# PICO_LCD.net
KiCad netlist of a schematic drawn in Altium Designer
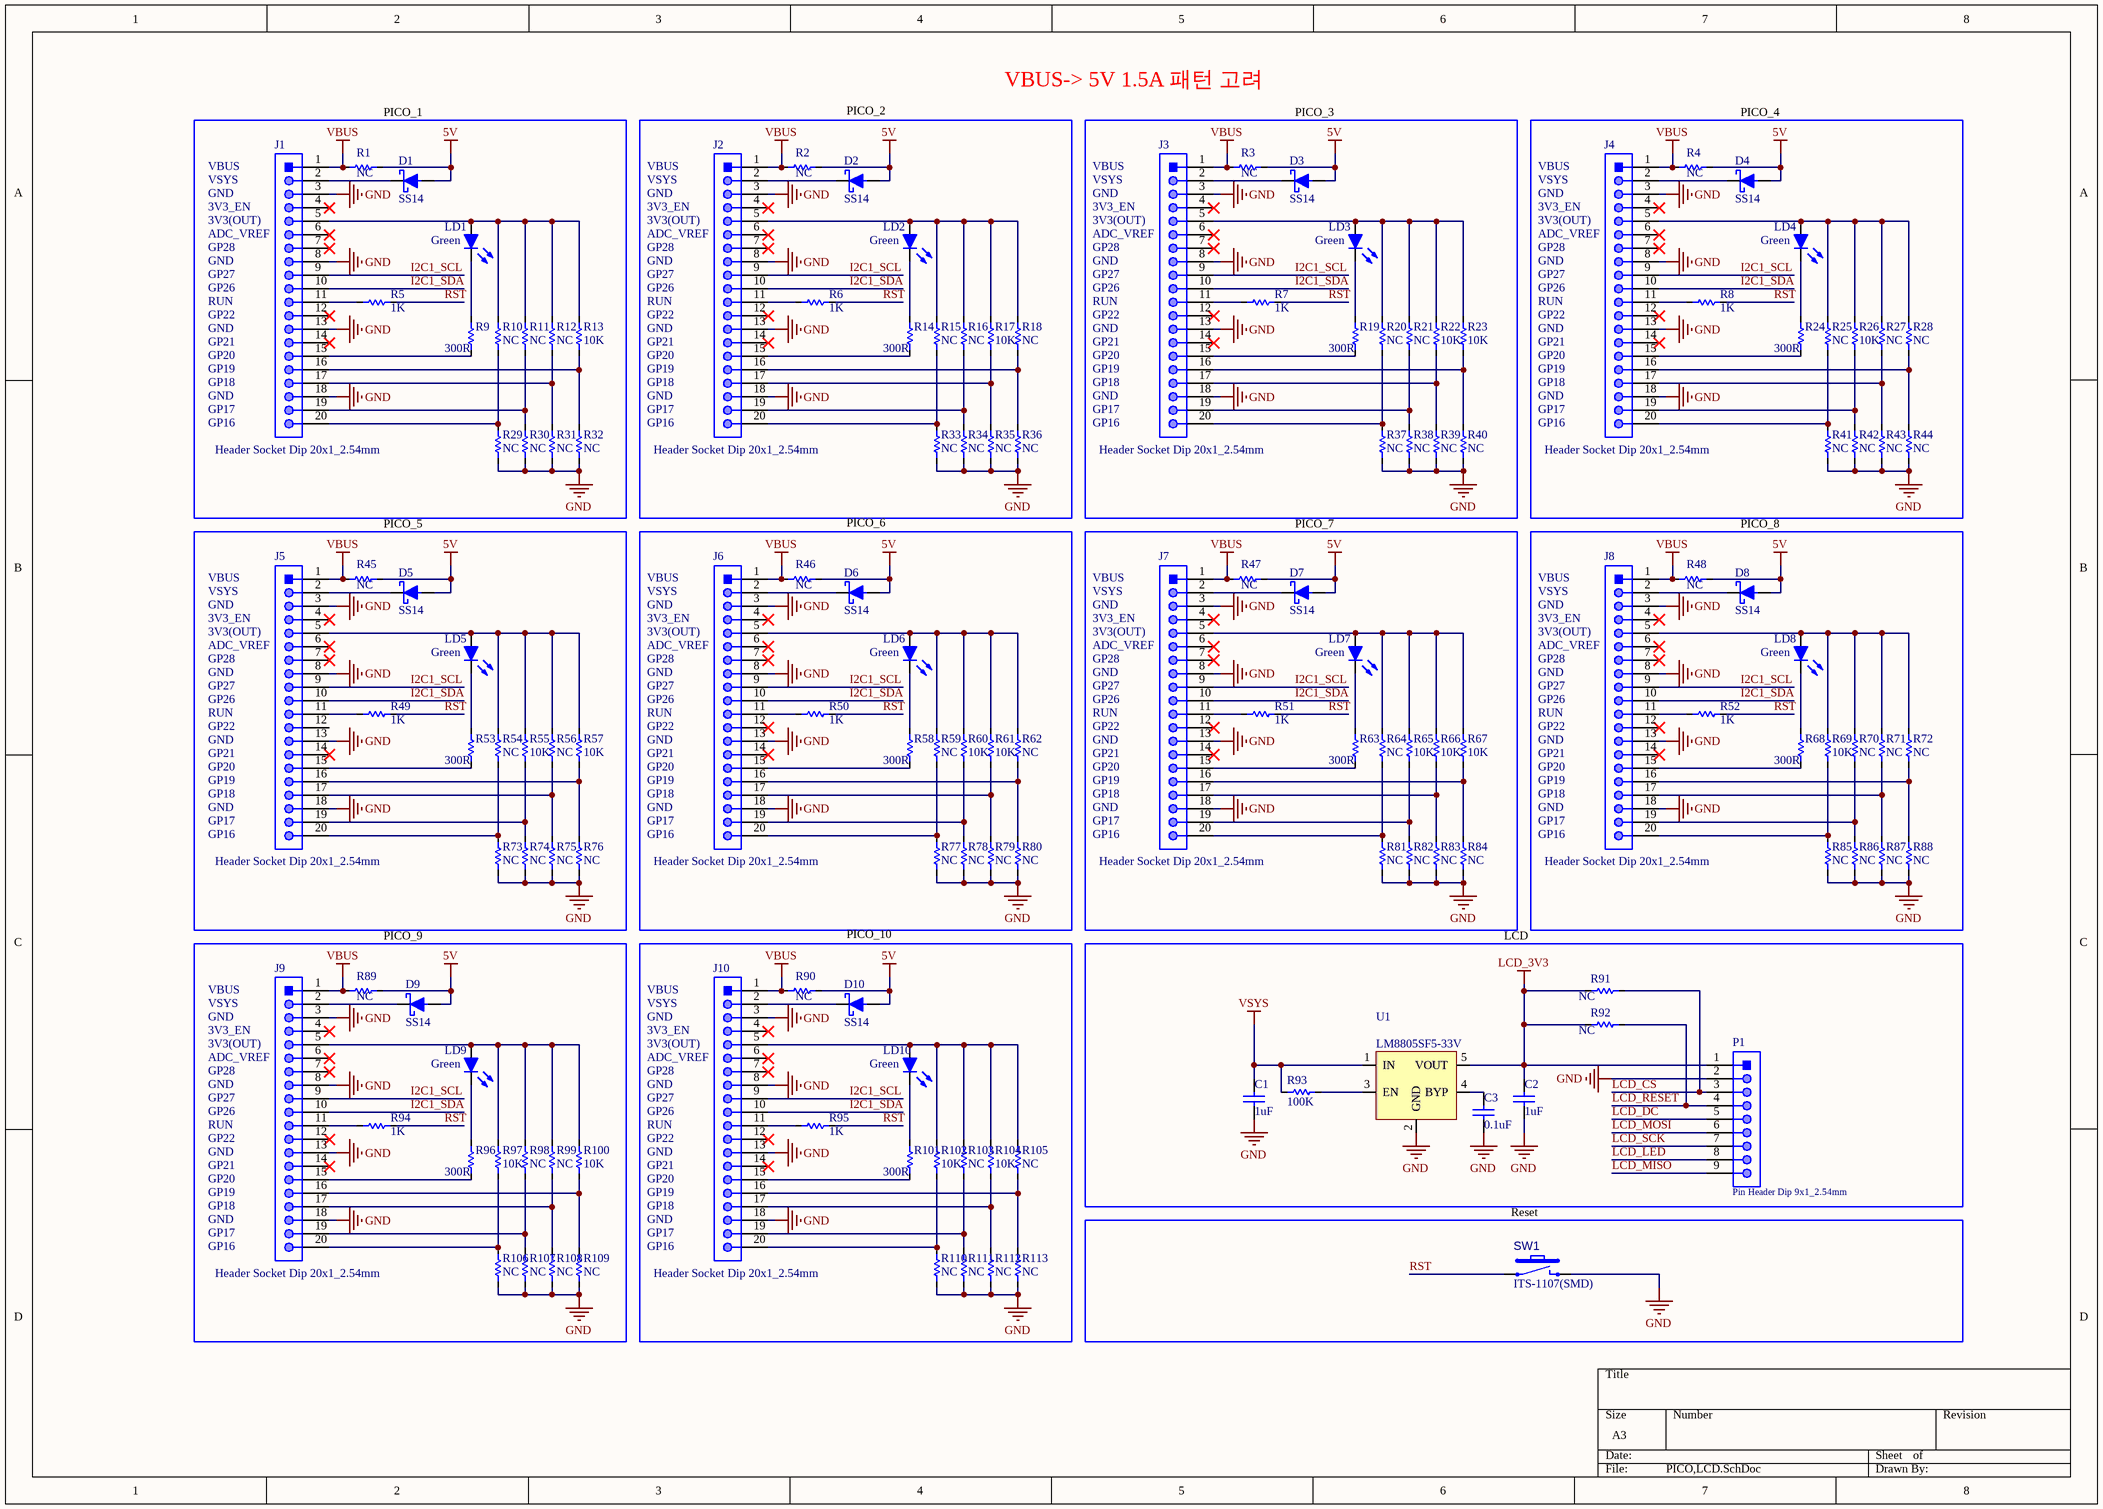
[diagram p0: PICO,LCD.SchDoc]

(export (version "E")
  (design (tool "Eeschema 10.0.6"))
  (components
    (comp (ref "C1")
      (value "1uF")
      (footprint "CAP-0603")
      (description "MLCC-0603(1608)")
      (libsource (lib "Jaden_Lib") (part "CAP-0603"))
    )
    (comp (ref "C2")
      (value "1uF")
      (footprint "CAP-0603")
      (description "MLCC-0603(1608)")
      (libsource (lib "Jaden_Lib") (part "CAP-0603"))
    )
    (comp (ref "C3")
      (value "0.1uF")
      (footprint "CAP-0603")
      (description "MLCC-0603(1608)")
      (libsource (lib "Jaden_Lib") (part "CAP-0603"))
    )
    (comp (ref "D1")
      (value "SS14")
      (footprint "DO-214AC/SMA")
      (description "DIODE SCHOTTKY 40V 1A SMA")
      (fields
        (field (name "MANUFACTURER") "ON Semiconductor")
        (field (name "OCTOPART") "https://octopart.com/ss14-on+semiconductor-29205033")
      )
      (libsource (lib "Jaden_Lib") (part "DIODE-Shottky SMA(DO-214AC)"))
    )
    (comp (ref "D2")
      (value "SS14")
      (footprint "DO-214AC/SMA")
      (description "DIODE SCHOTTKY 40V 1A SMA")
      (fields
        (field (name "MANUFACTURER") "ON Semiconductor")
        (field (name "OCTOPART") "https://octopart.com/ss14-on+semiconductor-29205033")
      )
      (libsource (lib "Jaden_Lib") (part "DIODE-Shottky SMA(DO-214AC)"))
    )
    (comp (ref "D3")
      (value "SS14")
      (footprint "DO-214AC/SMA")
      (description "DIODE SCHOTTKY 40V 1A SMA")
      (fields
        (field (name "MANUFACTURER") "ON Semiconductor")
        (field (name "OCTOPART") "https://octopart.com/ss14-on+semiconductor-29205033")
      )
      (libsource (lib "Jaden_Lib") (part "DIODE-Shottky SMA(DO-214AC)"))
    )
    (comp (ref "D4")
      (value "SS14")
      (footprint "DO-214AC/SMA")
      (description "DIODE SCHOTTKY 40V 1A SMA")
      (fields
        (field (name "MANUFACTURER") "ON Semiconductor")
        (field (name "OCTOPART") "https://octopart.com/ss14-on+semiconductor-29205033")
      )
      (libsource (lib "Jaden_Lib") (part "DIODE-Shottky SMA(DO-214AC)"))
    )
    (comp (ref "D5")
      (value "SS14")
      (footprint "DO-214AC/SMA")
      (description "DIODE SCHOTTKY 40V 1A SMA")
      (fields
        (field (name "MANUFACTURER") "ON Semiconductor")
        (field (name "OCTOPART") "https://octopart.com/ss14-on+semiconductor-29205033")
      )
      (libsource (lib "Jaden_Lib") (part "DIODE-Shottky SMA(DO-214AC)"))
    )
    (comp (ref "D6")
      (value "SS14")
      (footprint "DO-214AC/SMA")
      (description "DIODE SCHOTTKY 40V 1A SMA")
      (fields
        (field (name "MANUFACTURER") "ON Semiconductor")
        (field (name "OCTOPART") "https://octopart.com/ss14-on+semiconductor-29205033")
      )
      (libsource (lib "Jaden_Lib") (part "DIODE-Shottky SMA(DO-214AC)"))
    )
    (comp (ref "D7")
      (value "SS14")
      (footprint "DO-214AC/SMA")
      (description "DIODE SCHOTTKY 40V 1A SMA")
      (fields
        (field (name "MANUFACTURER") "ON Semiconductor")
        (field (name "OCTOPART") "https://octopart.com/ss14-on+semiconductor-29205033")
      )
      (libsource (lib "Jaden_Lib") (part "DIODE-Shottky SMA(DO-214AC)"))
    )
    (comp (ref "D8")
      (value "SS14")
      (footprint "DO-214AC/SMA")
      (description "DIODE SCHOTTKY 40V 1A SMA")
      (fields
        (field (name "MANUFACTURER") "ON Semiconductor")
        (field (name "OCTOPART") "https://octopart.com/ss14-on+semiconductor-29205033")
      )
      (libsource (lib "Jaden_Lib") (part "DIODE-Shottky SMA(DO-214AC)"))
    )
    (comp (ref "D9")
      (value "SS14")
      (footprint "DO-214AC/SMA")
      (description "DIODE SCHOTTKY 40V 1A SMA")
      (fields
        (field (name "MANUFACTURER") "ON Semiconductor")
        (field (name "OCTOPART") "https://octopart.com/ss14-on+semiconductor-29205033")
      )
      (libsource (lib "Jaden_Lib") (part "DIODE-Shottky SMA(DO-214AC)"))
    )
    (comp (ref "D10")
      (value "SS14")
      (footprint "DO-214AC/SMA")
      (description "DIODE SCHOTTKY 40V 1A SMA")
      (fields
        (field (name "MANUFACTURER") "ON Semiconductor")
        (field (name "OCTOPART") "https://octopart.com/ss14-on+semiconductor-29205033")
      )
      (libsource (lib "Jaden_Lib") (part "DIODE-Shottky SMA(DO-214AC)"))
    )
    (comp (ref "J1")
      (value "Header Socket Dip 20x1_2.54mm")
      (footprint "IDC-1X20(SOCKET)")
      (description "THT Vertical Header Socket WR-PHD, Pitch 2.54 mm, Single Row, 20 pins")
      (fields
        (field (name "MANUFACTURER_PART_NUMBER") "M20-7822046")
        (field (name "MOUSER PART NUMBER") "855-M20-7822046")
      )
      (libsource (lib "Jaden_Lib") (part "Header Socket 20x1_2.54mm"))
    )
    (comp (ref "J2")
      (value "Header Socket Dip 20x1_2.54mm")
      (footprint "IDC-1X20(SOCKET)")
      (description "THT Vertical Header Socket WR-PHD, Pitch 2.54 mm, Single Row, 20 pins")
      (fields
        (field (name "MANUFACTURER_PART_NUMBER") "M20-7822046")
        (field (name "MOUSER PART NUMBER") "855-M20-7822046")
      )
      (libsource (lib "Jaden_Lib") (part "Header Socket 20x1_2.54mm"))
    )
    (comp (ref "J3")
      (value "Header Socket Dip 20x1_2.54mm")
      (footprint "IDC-1X20(SOCKET)")
      (description "THT Vertical Header Socket WR-PHD, Pitch 2.54 mm, Single Row, 20 pins")
      (fields
        (field (name "MANUFACTURER_PART_NUMBER") "M20-7822046")
        (field (name "MOUSER PART NUMBER") "855-M20-7822046")
      )
      (libsource (lib "Jaden_Lib") (part "Header Socket 20x1_2.54mm"))
    )
    (comp (ref "J4")
      (value "Header Socket Dip 20x1_2.54mm")
      (footprint "IDC-1X20(SOCKET)")
      (description "THT Vertical Header Socket WR-PHD, Pitch 2.54 mm, Single Row, 20 pins")
      (fields
        (field (name "MANUFACTURER_PART_NUMBER") "M20-7822046")
        (field (name "MOUSER PART NUMBER") "855-M20-7822046")
      )
      (libsource (lib "Jaden_Lib") (part "Header Socket 20x1_2.54mm"))
    )
    (comp (ref "J5")
      (value "Header Socket Dip 20x1_2.54mm")
      (footprint "IDC-1X20(SOCKET)")
      (description "THT Vertical Header Socket WR-PHD, Pitch 2.54 mm, Single Row, 20 pins")
      (fields
        (field (name "MANUFACTURER_PART_NUMBER") "M20-7822046")
        (field (name "MOUSER PART NUMBER") "855-M20-7822046")
      )
      (libsource (lib "Jaden_Lib") (part "Header Socket 20x1_2.54mm"))
    )
    (comp (ref "J6")
      (value "Header Socket Dip 20x1_2.54mm")
      (footprint "IDC-1X20(SOCKET)")
      (description "THT Vertical Header Socket WR-PHD, Pitch 2.54 mm, Single Row, 20 pins")
      (fields
        (field (name "MANUFACTURER_PART_NUMBER") "M20-7822046")
        (field (name "MOUSER PART NUMBER") "855-M20-7822046")
      )
      (libsource (lib "Jaden_Lib") (part "Header Socket 20x1_2.54mm"))
    )
    (comp (ref "J7")
      (value "Header Socket Dip 20x1_2.54mm")
      (footprint "IDC-1X20(SOCKET)")
      (description "THT Vertical Header Socket WR-PHD, Pitch 2.54 mm, Single Row, 20 pins")
      (fields
        (field (name "MANUFACTURER_PART_NUMBER") "M20-7822046")
        (field (name "MOUSER PART NUMBER") "855-M20-7822046")
      )
      (libsource (lib "Jaden_Lib") (part "Header Socket 20x1_2.54mm"))
    )
    (comp (ref "J8")
      (value "Header Socket Dip 20x1_2.54mm")
      (footprint "IDC-1X20(SOCKET)")
      (description "THT Vertical Header Socket WR-PHD, Pitch 2.54 mm, Single Row, 20 pins")
      (fields
        (field (name "MANUFACTURER_PART_NUMBER") "M20-7822046")
        (field (name "MOUSER PART NUMBER") "855-M20-7822046")
      )
      (libsource (lib "Jaden_Lib") (part "Header Socket 20x1_2.54mm"))
    )
    (comp (ref "J9")
      (value "Header Socket Dip 20x1_2.54mm")
      (footprint "IDC-1X20(SOCKET)")
      (description "THT Vertical Header Socket WR-PHD, Pitch 2.54 mm, Single Row, 20 pins")
      (fields
        (field (name "MANUFACTURER_PART_NUMBER") "M20-7822046")
        (field (name "MOUSER PART NUMBER") "855-M20-7822046")
      )
      (libsource (lib "Jaden_Lib") (part "Header Socket 20x1_2.54mm"))
    )
    (comp (ref "J10")
      (value "Header Socket Dip 20x1_2.54mm")
      (footprint "IDC-1X20(SOCKET)")
      (description "THT Vertical Header Socket WR-PHD, Pitch 2.54 mm, Single Row, 20 pins")
      (fields
        (field (name "MANUFACTURER_PART_NUMBER") "M20-7822046")
        (field (name "MOUSER PART NUMBER") "855-M20-7822046")
      )
      (libsource (lib "Jaden_Lib") (part "Header Socket 20x1_2.54mm"))
    )
    (comp (ref "LD1")
      (value "Green")
      (footprint "LED-0603-GREEN")
      (description "LED-0603")
      (libsource (lib "Jaden_Lib") (part "GREEN LED-0603"))
    )
    (comp (ref "LD2")
      (value "Green")
      (footprint "LED-0603-GREEN")
      (description "LED-0603")
      (libsource (lib "Jaden_Lib") (part "GREEN LED-0603"))
    )
    (comp (ref "LD3")
      (value "Green")
      (footprint "LED-0603-GREEN")
      (description "LED-0603")
      (libsource (lib "Jaden_Lib") (part "GREEN LED-0603"))
    )
    (comp (ref "LD4")
      (value "Green")
      (footprint "LED-0603-GREEN")
      (description "LED-0603")
      (libsource (lib "Jaden_Lib") (part "GREEN LED-0603"))
    )
    (comp (ref "LD5")
      (value "Green")
      (footprint "LED-0603-GREEN")
      (description "LED-0603")
      (libsource (lib "Jaden_Lib") (part "GREEN LED-0603"))
    )
    (comp (ref "LD6")
      (value "Green")
      (footprint "LED-0603-GREEN")
      (description "LED-0603")
      (libsource (lib "Jaden_Lib") (part "GREEN LED-0603"))
    )
    (comp (ref "LD7")
      (value "Green")
      (footprint "LED-0603-GREEN")
      (description "LED-0603")
      (libsource (lib "Jaden_Lib") (part "GREEN LED-0603"))
    )
    (comp (ref "LD8")
      (value "Green")
      (footprint "LED-0603-GREEN")
      (description "LED-0603")
      (libsource (lib "Jaden_Lib") (part "GREEN LED-0603"))
    )
    (comp (ref "LD9")
      (value "Green")
      (footprint "LED-0603-GREEN")
      (description "LED-0603")
      (libsource (lib "Jaden_Lib") (part "GREEN LED-0603"))
    )
    (comp (ref "LD10")
      (value "Green")
      (footprint "LED-0603-GREEN")
      (description "LED-0603")
      (libsource (lib "Jaden_Lib") (part "GREEN LED-0603"))
    )
    (comp (ref "P1")
      (value "Pin Header Dip 9x1_2.54mm")
      (footprint "LCD(PIN HEADER9X1_2.54)")
      (description "THT Vertical Pin Header WR-PHD, Pitch 2.54 mm, Single Row, 9 pins")
      (fields
        (field (name "PART NUMBER") "61300911121")
        (field (name "MANUFACTURER") "Wurth Elektronik")
        (field (name "PUBLISHER") "WurthElektronik")
      )
      (libsource (lib "Jaden_Lib") (part "Pin Header 9x1_2.54mm"))
    )
    (comp (ref "R1")
      (value "NC")
      (footprint "RES-0603")
      (description "Chip Resistor 0603(1608)")
      (fields (field (name "TOLERANCE") "1%") (field (name "MANUFACTURER") "Yageo"))
      (libsource (lib "Jaden_Lib") (part "RES-0603"))
    )
    (comp (ref "R2")
      (value "NC")
      (footprint "RES-0603")
      (description "Chip Resistor 0603(1608)")
      (fields (field (name "TOLERANCE") "1%") (field (name "MANUFACTURER") "Yageo"))
      (libsource (lib "Jaden_Lib") (part "RES-0603"))
    )
    (comp (ref "R3")
      (value "NC")
      (footprint "RES-0603")
      (description "Chip Resistor 0603(1608)")
      (fields (field (name "TOLERANCE") "1%") (field (name "MANUFACTURER") "Yageo"))
      (libsource (lib "Jaden_Lib") (part "RES-0603"))
    )
    (comp (ref "R4")
      (value "NC")
      (footprint "RES-0603")
      (description "Chip Resistor 0603(1608)")
      (fields (field (name "TOLERANCE") "1%") (field (name "MANUFACTURER") "Yageo"))
      (libsource (lib "Jaden_Lib") (part "RES-0603"))
    )
    (comp (ref "R5")
      (value "1K")
      (footprint "RES-0603")
      (description "Chip Resistor 0603(1608)")
      (fields (field (name "TOLERANCE") "1%") (field (name "MANUFACTURER") "Yageo"))
      (libsource (lib "Jaden_Lib") (part "RES-0603"))
    )
    (comp (ref "R6")
      (value "1K")
      (footprint "RES-0603")
      (description "Chip Resistor 0603(1608)")
      (fields (field (name "TOLERANCE") "1%") (field (name "MANUFACTURER") "Yageo"))
      (libsource (lib "Jaden_Lib") (part "RES-0603"))
    )
    (comp (ref "R7")
      (value "1K")
      (footprint "RES-0603")
      (description "Chip Resistor 0603(1608)")
      (fields (field (name "TOLERANCE") "1%") (field (name "MANUFACTURER") "Yageo"))
      (libsource (lib "Jaden_Lib") (part "RES-0603"))
    )
    (comp (ref "R8")
      (value "1K")
      (footprint "RES-0603")
      (description "Chip Resistor 0603(1608)")
      (fields (field (name "TOLERANCE") "1%") (field (name "MANUFACTURER") "Yageo"))
      (libsource (lib "Jaden_Lib") (part "RES-0603"))
    )
    (comp (ref "R9")
      (value "300R")
      (footprint "RES-0603")
      (description "Chip Resistor 0603(1608)")
      (fields (field (name "TOLERANCE") "1%") (field (name "MANUFACTURER") "Yageo"))
      (libsource (lib "Jaden_Lib") (part "RES-0603"))
    )
    (comp (ref "R10")
      (value "NC")
      (footprint "RES-0603")
      (description "Chip Resistor 0603(1608)")
      (fields (field (name "TOLERANCE") "1%") (field (name "MANUFACTURER") "Yageo"))
      (libsource (lib "Jaden_Lib") (part "RES-0603"))
    )
    (comp (ref "R11")
      (value "NC")
      (footprint "RES-0603")
      (description "Chip Resistor 0603(1608)")
      (fields (field (name "TOLERANCE") "1%") (field (name "MANUFACTURER") "Yageo"))
      (libsource (lib "Jaden_Lib") (part "RES-0603"))
    )
    (comp (ref "R12")
      (value "NC")
      (footprint "RES-0603")
      (description "Chip Resistor 0603(1608)")
      (fields (field (name "TOLERANCE") "1%") (field (name "MANUFACTURER") "Yageo"))
      (libsource (lib "Jaden_Lib") (part "RES-0603"))
    )
    (comp (ref "R13")
      (value "10K")
      (footprint "RES-0603")
      (description "Chip Resistor 0603(1608)")
      (fields (field (name "TOLERANCE") "1%") (field (name "MANUFACTURER") "Yageo"))
      (libsource (lib "Jaden_Lib") (part "RES-0603"))
    )
    (comp (ref "R14")
      (value "300R")
      (footprint "RES-0603")
      (description "Chip Resistor 0603(1608)")
      (fields (field (name "TOLERANCE") "1%") (field (name "MANUFACTURER") "Yageo"))
      (libsource (lib "Jaden_Lib") (part "RES-0603"))
    )
    (comp (ref "R15")
      (value "NC")
      (footprint "RES-0603")
      (description "Chip Resistor 0603(1608)")
      (fields (field (name "TOLERANCE") "1%") (field (name "MANUFACTURER") "Yageo"))
      (libsource (lib "Jaden_Lib") (part "RES-0603"))
    )
    (comp (ref "R16")
      (value "NC")
      (footprint "RES-0603")
      (description "Chip Resistor 0603(1608)")
      (fields (field (name "TOLERANCE") "1%") (field (name "MANUFACTURER") "Yageo"))
      (libsource (lib "Jaden_Lib") (part "RES-0603"))
    )
    (comp (ref "R17")
      (value "10K")
      (footprint "RES-0603")
      (description "Chip Resistor 0603(1608)")
      (fields (field (name "TOLERANCE") "1%") (field (name "MANUFACTURER") "Yageo"))
      (libsource (lib "Jaden_Lib") (part "RES-0603"))
    )
    (comp (ref "R18")
      (value "NC")
      (footprint "RES-0603")
      (description "Chip Resistor 0603(1608)")
      (fields (field (name "TOLERANCE") "1%") (field (name "MANUFACTURER") "Yageo"))
      (libsource (lib "Jaden_Lib") (part "RES-0603"))
    )
    (comp (ref "R19")
      (value "300R")
      (footprint "RES-0603")
      (description "Chip Resistor 0603(1608)")
      (fields (field (name "TOLERANCE") "1%") (field (name "MANUFACTURER") "Yageo"))
      (libsource (lib "Jaden_Lib") (part "RES-0603"))
    )
    (comp (ref "R20")
      (value "NC")
      (footprint "RES-0603")
      (description "Chip Resistor 0603(1608)")
      (fields (field (name "TOLERANCE") "1%") (field (name "MANUFACTURER") "Yageo"))
      (libsource (lib "Jaden_Lib") (part "RES-0603"))
    )
    (comp (ref "R21")
      (value "NC")
      (footprint "RES-0603")
      (description "Chip Resistor 0603(1608)")
      (fields (field (name "TOLERANCE") "1%") (field (name "MANUFACTURER") "Yageo"))
      (libsource (lib "Jaden_Lib") (part "RES-0603"))
    )
    (comp (ref "R22")
      (value "10K")
      (footprint "RES-0603")
      (description "Chip Resistor 0603(1608)")
      (fields (field (name "TOLERANCE") "1%") (field (name "MANUFACTURER") "Yageo"))
      (libsource (lib "Jaden_Lib") (part "RES-0603"))
    )
    (comp (ref "R23")
      (value "10K")
      (footprint "RES-0603")
      (description "Chip Resistor 0603(1608)")
      (fields (field (name "TOLERANCE") "1%") (field (name "MANUFACTURER") "Yageo"))
      (libsource (lib "Jaden_Lib") (part "RES-0603"))
    )
    (comp (ref "R24")
      (value "300R")
      (footprint "RES-0603")
      (description "Chip Resistor 0603(1608)")
      (fields (field (name "TOLERANCE") "1%") (field (name "MANUFACTURER") "Yageo"))
      (libsource (lib "Jaden_Lib") (part "RES-0603"))
    )
    (comp (ref "R25")
      (value "NC")
      (footprint "RES-0603")
      (description "Chip Resistor 0603(1608)")
      (fields (field (name "TOLERANCE") "1%") (field (name "MANUFACTURER") "Yageo"))
      (libsource (lib "Jaden_Lib") (part "RES-0603"))
    )
    (comp (ref "R26")
      (value "10K")
      (footprint "RES-0603")
      (description "Chip Resistor 0603(1608)")
      (fields (field (name "TOLERANCE") "1%") (field (name "MANUFACTURER") "Yageo"))
      (libsource (lib "Jaden_Lib") (part "RES-0603"))
    )
    (comp (ref "R27")
      (value "NC")
      (footprint "RES-0603")
      (description "Chip Resistor 0603(1608)")
      (fields (field (name "TOLERANCE") "1%") (field (name "MANUFACTURER") "Yageo"))
      (libsource (lib "Jaden_Lib") (part "RES-0603"))
    )
    (comp (ref "R28")
      (value "NC")
      (footprint "RES-0603")
      (description "Chip Resistor 0603(1608)")
      (fields (field (name "TOLERANCE") "1%") (field (name "MANUFACTURER") "Yageo"))
      (libsource (lib "Jaden_Lib") (part "RES-0603"))
    )
    (comp (ref "R29")
      (value "NC")
      (footprint "RES-0603")
      (description "Chip Resistor 0603(1608)")
      (fields (field (name "TOLERANCE") "1%") (field (name "MANUFACTURER") "Yageo"))
      (libsource (lib "Jaden_Lib") (part "RES-0603"))
    )
    (comp (ref "R30")
      (value "NC")
      (footprint "RES-0603")
      (description "Chip Resistor 0603(1608)")
      (fields (field (name "TOLERANCE") "1%") (field (name "MANUFACTURER") "Yageo"))
      (libsource (lib "Jaden_Lib") (part "RES-0603"))
    )
    (comp (ref "R31")
      (value "NC")
      (footprint "RES-0603")
      (description "Chip Resistor 0603(1608)")
      (fields (field (name "TOLERANCE") "1%") (field (name "MANUFACTURER") "Yageo"))
      (libsource (lib "Jaden_Lib") (part "RES-0603"))
    )
    (comp (ref "R32")
      (value "NC")
      (footprint "RES-0603")
      (description "Chip Resistor 0603(1608)")
      (fields (field (name "TOLERANCE") "1%") (field (name "MANUFACTURER") "Yageo"))
      (libsource (lib "Jaden_Lib") (part "RES-0603"))
    )
    (comp (ref "R33")
      (value "NC")
      (footprint "RES-0603")
      (description "Chip Resistor 0603(1608)")
      (fields (field (name "TOLERANCE") "1%") (field (name "MANUFACTURER") "Yageo"))
      (libsource (lib "Jaden_Lib") (part "RES-0603"))
    )
    (comp (ref "R34")
      (value "NC")
      (footprint "RES-0603")
      (description "Chip Resistor 0603(1608)")
      (fields (field (name "TOLERANCE") "1%") (field (name "MANUFACTURER") "Yageo"))
      (libsource (lib "Jaden_Lib") (part "RES-0603"))
    )
    (comp (ref "R35")
      (value "NC")
      (footprint "RES-0603")
      (description "Chip Resistor 0603(1608)")
      (fields (field (name "TOLERANCE") "1%") (field (name "MANUFACTURER") "Yageo"))
      (libsource (lib "Jaden_Lib") (part "RES-0603"))
    )
    (comp (ref "R36")
      (value "NC")
      (footprint "RES-0603")
      (description "Chip Resistor 0603(1608)")
      (fields (field (name "TOLERANCE") "1%") (field (name "MANUFACTURER") "Yageo"))
      (libsource (lib "Jaden_Lib") (part "RES-0603"))
    )
    (comp (ref "R37")
      (value "NC")
      (footprint "RES-0603")
      (description "Chip Resistor 0603(1608)")
      (fields (field (name "TOLERANCE") "1%") (field (name "MANUFACTURER") "Yageo"))
      (libsource (lib "Jaden_Lib") (part "RES-0603"))
    )
    (comp (ref "R38")
      (value "NC")
      (footprint "RES-0603")
      (description "Chip Resistor 0603(1608)")
      (fields (field (name "TOLERANCE") "1%") (field (name "MANUFACTURER") "Yageo"))
      (libsource (lib "Jaden_Lib") (part "RES-0603"))
    )
    (comp (ref "R39")
      (value "NC")
      (footprint "RES-0603")
      (description "Chip Resistor 0603(1608)")
      (fields (field (name "TOLERANCE") "1%") (field (name "MANUFACTURER") "Yageo"))
      (libsource (lib "Jaden_Lib") (part "RES-0603"))
    )
    (comp (ref "R40")
      (value "NC")
      (footprint "RES-0603")
      (description "Chip Resistor 0603(1608)")
      (fields (field (name "TOLERANCE") "1%") (field (name "MANUFACTURER") "Yageo"))
      (libsource (lib "Jaden_Lib") (part "RES-0603"))
    )
    (comp (ref "R41")
      (value "NC")
      (footprint "RES-0603")
      (description "Chip Resistor 0603(1608)")
      (fields (field (name "TOLERANCE") "1%") (field (name "MANUFACTURER") "Yageo"))
      (libsource (lib "Jaden_Lib") (part "RES-0603"))
    )
    (comp (ref "R42")
      (value "NC")
      (footprint "RES-0603")
      (description "Chip Resistor 0603(1608)")
      (fields (field (name "TOLERANCE") "1%") (field (name "MANUFACTURER") "Yageo"))
      (libsource (lib "Jaden_Lib") (part "RES-0603"))
    )
    (comp (ref "R43")
      (value "NC")
      (footprint "RES-0603")
      (description "Chip Resistor 0603(1608)")
      (fields (field (name "TOLERANCE") "1%") (field (name "MANUFACTURER") "Yageo"))
      (libsource (lib "Jaden_Lib") (part "RES-0603"))
    )
    (comp (ref "R44")
      (value "NC")
      (footprint "RES-0603")
      (description "Chip Resistor 0603(1608)")
      (fields (field (name "TOLERANCE") "1%") (field (name "MANUFACTURER") "Yageo"))
      (libsource (lib "Jaden_Lib") (part "RES-0603"))
    )
    (comp (ref "R45")
      (value "NC")
      (footprint "RES-0603")
      (description "Chip Resistor 0603(1608)")
      (fields (field (name "TOLERANCE") "1%") (field (name "MANUFACTURER") "Yageo"))
      (libsource (lib "Jaden_Lib") (part "RES-0603"))
    )
    (comp (ref "R46")
      (value "NC")
      (footprint "RES-0603")
      (description "Chip Resistor 0603(1608)")
      (fields (field (name "TOLERANCE") "1%") (field (name "MANUFACTURER") "Yageo"))
      (libsource (lib "Jaden_Lib") (part "RES-0603"))
    )
    (comp (ref "R47")
      (value "NC")
      (footprint "RES-0603")
      (description "Chip Resistor 0603(1608)")
      (fields (field (name "TOLERANCE") "1%") (field (name "MANUFACTURER") "Yageo"))
      (libsource (lib "Jaden_Lib") (part "RES-0603"))
    )
    (comp (ref "R48")
      (value "NC")
      (footprint "RES-0603")
      (description "Chip Resistor 0603(1608)")
      (fields (field (name "TOLERANCE") "1%") (field (name "MANUFACTURER") "Yageo"))
      (libsource (lib "Jaden_Lib") (part "RES-0603"))
    )
    (comp (ref "R49")
      (value "1K")
      (footprint "RES-0603")
      (description "Chip Resistor 0603(1608)")
      (fields (field (name "TOLERANCE") "1%") (field (name "MANUFACTURER") "Yageo"))
      (libsource (lib "Jaden_Lib") (part "RES-0603"))
    )
    (comp (ref "R50")
      (value "1K")
      (footprint "RES-0603")
      (description "Chip Resistor 0603(1608)")
      (fields (field (name "TOLERANCE") "1%") (field (name "MANUFACTURER") "Yageo"))
      (libsource (lib "Jaden_Lib") (part "RES-0603"))
    )
    (comp (ref "R51")
      (value "1K")
      (footprint "RES-0603")
      (description "Chip Resistor 0603(1608)")
      (fields (field (name "TOLERANCE") "1%") (field (name "MANUFACTURER") "Yageo"))
      (libsource (lib "Jaden_Lib") (part "RES-0603"))
    )
    (comp (ref "R52")
      (value "1K")
      (footprint "RES-0603")
      (description "Chip Resistor 0603(1608)")
      (fields (field (name "TOLERANCE") "1%") (field (name "MANUFACTURER") "Yageo"))
      (libsource (lib "Jaden_Lib") (part "RES-0603"))
    )
    (comp (ref "R53")
      (value "300R")
      (footprint "RES-0603")
      (description "Chip Resistor 0603(1608)")
      (fields (field (name "TOLERANCE") "1%") (field (name "MANUFACTURER") "Yageo"))
      (libsource (lib "Jaden_Lib") (part "RES-0603"))
    )
    (comp (ref "R54")
      (value "NC")
      (footprint "RES-0603")
      (description "Chip Resistor 0603(1608)")
      (fields (field (name "TOLERANCE") "1%") (field (name "MANUFACTURER") "Yageo"))
      (libsource (lib "Jaden_Lib") (part "RES-0603"))
    )
    (comp (ref "R55")
      (value "10K")
      (footprint "RES-0603")
      (description "Chip Resistor 0603(1608)")
      (fields (field (name "TOLERANCE") "1%") (field (name "MANUFACTURER") "Yageo"))
      (libsource (lib "Jaden_Lib") (part "RES-0603"))
    )
    (comp (ref "R56")
      (value "NC")
      (footprint "RES-0603")
      (description "Chip Resistor 0603(1608)")
      (fields (field (name "TOLERANCE") "1%") (field (name "MANUFACTURER") "Yageo"))
      (libsource (lib "Jaden_Lib") (part "RES-0603"))
    )
    (comp (ref "R57")
      (value "10K")
      (footprint "RES-0603")
      (description "Chip Resistor 0603(1608)")
      (fields (field (name "TOLERANCE") "1%") (field (name "MANUFACTURER") "Yageo"))
      (libsource (lib "Jaden_Lib") (part "RES-0603"))
    )
    (comp (ref "R58")
      (value "300R")
      (footprint "RES-0603")
      (description "Chip Resistor 0603(1608)")
      (fields (field (name "TOLERANCE") "1%") (field (name "MANUFACTURER") "Yageo"))
      (libsource (lib "Jaden_Lib") (part "RES-0603"))
    )
    (comp (ref "R59")
      (value "NC")
      (footprint "RES-0603")
      (description "Chip Resistor 0603(1608)")
      (fields (field (name "TOLERANCE") "1%") (field (name "MANUFACTURER") "Yageo"))
      (libsource (lib "Jaden_Lib") (part "RES-0603"))
    )
    (comp (ref "R60")
      (value "10K")
      (footprint "RES-0603")
      (description "Chip Resistor 0603(1608)")
      (fields (field (name "TOLERANCE") "1%") (field (name "MANUFACTURER") "Yageo"))
      (libsource (lib "Jaden_Lib") (part "RES-0603"))
    )
    (comp (ref "R61")
      (value "10K")
      (footprint "RES-0603")
      (description "Chip Resistor 0603(1608)")
      (fields (field (name "TOLERANCE") "1%") (field (name "MANUFACTURER") "Yageo"))
      (libsource (lib "Jaden_Lib") (part "RES-0603"))
    )
    (comp (ref "R62")
      (value "NC")
      (footprint "RES-0603")
      (description "Chip Resistor 0603(1608)")
      (fields (field (name "TOLERANCE") "1%") (field (name "MANUFACTURER") "Yageo"))
      (libsource (lib "Jaden_Lib") (part "RES-0603"))
    )
    (comp (ref "R63")
      (value "300R")
      (footprint "RES-0603")
      (description "Chip Resistor 0603(1608)")
      (fields (field (name "TOLERANCE") "1%") (field (name "MANUFACTURER") "Yageo"))
      (libsource (lib "Jaden_Lib") (part "RES-0603"))
    )
    (comp (ref "R64")
      (value "NC")
      (footprint "RES-0603")
      (description "Chip Resistor 0603(1608)")
      (fields (field (name "TOLERANCE") "1%") (field (name "MANUFACTURER") "Yageo"))
      (libsource (lib "Jaden_Lib") (part "RES-0603"))
    )
    (comp (ref "R65")
      (value "10K")
      (footprint "RES-0603")
      (description "Chip Resistor 0603(1608)")
      (fields (field (name "TOLERANCE") "1%") (field (name "MANUFACTURER") "Yageo"))
      (libsource (lib "Jaden_Lib") (part "RES-0603"))
    )
    (comp (ref "R66")
      (value "10K")
      (footprint "RES-0603")
      (description "Chip Resistor 0603(1608)")
      (fields (field (name "TOLERANCE") "1%") (field (name "MANUFACTURER") "Yageo"))
      (libsource (lib "Jaden_Lib") (part "RES-0603"))
    )
    (comp (ref "R67")
      (value "10K")
      (footprint "RES-0603")
      (description "Chip Resistor 0603(1608)")
      (fields (field (name "TOLERANCE") "1%") (field (name "MANUFACTURER") "Yageo"))
      (libsource (lib "Jaden_Lib") (part "RES-0603"))
    )
    (comp (ref "R68")
      (value "300R")
      (footprint "RES-0603")
      (description "Chip Resistor 0603(1608)")
      (fields (field (name "TOLERANCE") "1%") (field (name "MANUFACTURER") "Yageo"))
      (libsource (lib "Jaden_Lib") (part "RES-0603"))
    )
    (comp (ref "R69")
      (value "10K")
      (footprint "RES-0603")
      (description "Chip Resistor 0603(1608)")
      (fields (field (name "TOLERANCE") "1%") (field (name "MANUFACTURER") "Yageo"))
      (libsource (lib "Jaden_Lib") (part "RES-0603"))
    )
    (comp (ref "R70")
      (value "NC")
      (footprint "RES-0603")
      (description "Chip Resistor 0603(1608)")
      (fields (field (name "TOLERANCE") "1%") (field (name "MANUFACTURER") "Yageo"))
      (libsource (lib "Jaden_Lib") (part "RES-0603"))
    )
    (comp (ref "R71")
      (value "NC")
      (footprint "RES-0603")
      (description "Chip Resistor 0603(1608)")
      (fields (field (name "TOLERANCE") "1%") (field (name "MANUFACTURER") "Yageo"))
      (libsource (lib "Jaden_Lib") (part "RES-0603"))
    )
    (comp (ref "R72")
      (value "NC")
      (footprint "RES-0603")
      (description "Chip Resistor 0603(1608)")
      (fields (field (name "TOLERANCE") "1%") (field (name "MANUFACTURER") "Yageo"))
      (libsource (lib "Jaden_Lib") (part "RES-0603"))
    )
    (comp (ref "R73")
      (value "NC")
      (footprint "RES-0603")
      (description "Chip Resistor 0603(1608)")
      (fields (field (name "TOLERANCE") "1%") (field (name "MANUFACTURER") "Yageo"))
      (libsource (lib "Jaden_Lib") (part "RES-0603"))
    )
    (comp (ref "R74")
      (value "NC")
      (footprint "RES-0603")
      (description "Chip Resistor 0603(1608)")
      (fields (field (name "TOLERANCE") "1%") (field (name "MANUFACTURER") "Yageo"))
      (libsource (lib "Jaden_Lib") (part "RES-0603"))
    )
    (comp (ref "R75")
      (value "NC")
      (footprint "RES-0603")
      (description "Chip Resistor 0603(1608)")
      (fields (field (name "TOLERANCE") "1%") (field (name "MANUFACTURER") "Yageo"))
      (libsource (lib "Jaden_Lib") (part "RES-0603"))
    )
    (comp (ref "R76")
      (value "NC")
      (footprint "RES-0603")
      (description "Chip Resistor 0603(1608)")
      (fields (field (name "TOLERANCE") "1%") (field (name "MANUFACTURER") "Yageo"))
      (libsource (lib "Jaden_Lib") (part "RES-0603"))
    )
    (comp (ref "R77")
      (value "NC")
      (footprint "RES-0603")
      (description "Chip Resistor 0603(1608)")
      (fields (field (name "TOLERANCE") "1%") (field (name "MANUFACTURER") "Yageo"))
      (libsource (lib "Jaden_Lib") (part "RES-0603"))
    )
    (comp (ref "R78")
      (value "NC")
      (footprint "RES-0603")
      (description "Chip Resistor 0603(1608)")
      (fields (field (name "TOLERANCE") "1%") (field (name "MANUFACTURER") "Yageo"))
      (libsource (lib "Jaden_Lib") (part "RES-0603"))
    )
    (comp (ref "R79")
      (value "NC")
      (footprint "RES-0603")
      (description "Chip Resistor 0603(1608)")
      (fields (field (name "TOLERANCE") "1%") (field (name "MANUFACTURER") "Yageo"))
      (libsource (lib "Jaden_Lib") (part "RES-0603"))
    )
    (comp (ref "R80")
      (value "NC")
      (footprint "RES-0603")
      (description "Chip Resistor 0603(1608)")
      (fields (field (name "TOLERANCE") "1%") (field (name "MANUFACTURER") "Yageo"))
      (libsource (lib "Jaden_Lib") (part "RES-0603"))
    )
    (comp (ref "R81")
      (value "NC")
      (footprint "RES-0603")
      (description "Chip Resistor 0603(1608)")
      (fields (field (name "TOLERANCE") "1%") (field (name "MANUFACTURER") "Yageo"))
      (libsource (lib "Jaden_Lib") (part "RES-0603"))
    )
    (comp (ref "R82")
      (value "NC")
      (footprint "RES-0603")
      (description "Chip Resistor 0603(1608)")
      (fields (field (name "TOLERANCE") "1%") (field (name "MANUFACTURER") "Yageo"))
      (libsource (lib "Jaden_Lib") (part "RES-0603"))
    )
    (comp (ref "R83")
      (value "NC")
      (footprint "RES-0603")
      (description "Chip Resistor 0603(1608)")
      (fields (field (name "TOLERANCE") "1%") (field (name "MANUFACTURER") "Yageo"))
      (libsource (lib "Jaden_Lib") (part "RES-0603"))
    )
    (comp (ref "R84")
      (value "NC")
      (footprint "RES-0603")
      (description "Chip Resistor 0603(1608)")
      (fields (field (name "TOLERANCE") "1%") (field (name "MANUFACTURER") "Yageo"))
      (libsource (lib "Jaden_Lib") (part "RES-0603"))
    )
    (comp (ref "R85")
      (value "NC")
      (footprint "RES-0603")
      (description "Chip Resistor 0603(1608)")
      (fields (field (name "TOLERANCE") "1%") (field (name "MANUFACTURER") "Yageo"))
      (libsource (lib "Jaden_Lib") (part "RES-0603"))
    )
    (comp (ref "R86")
      (value "NC")
      (footprint "RES-0603")
      (description "Chip Resistor 0603(1608)")
      (fields (field (name "TOLERANCE") "1%") (field (name "MANUFACTURER") "Yageo"))
      (libsource (lib "Jaden_Lib") (part "RES-0603"))
    )
    (comp (ref "R87")
      (value "NC")
      (footprint "RES-0603")
      (description "Chip Resistor 0603(1608)")
      (fields (field (name "TOLERANCE") "1%") (field (name "MANUFACTURER") "Yageo"))
      (libsource (lib "Jaden_Lib") (part "RES-0603"))
    )
    (comp (ref "R88")
      (value "NC")
      (footprint "RES-0603")
      (description "Chip Resistor 0603(1608)")
      (fields (field (name "TOLERANCE") "1%") (field (name "MANUFACTURER") "Yageo"))
      (libsource (lib "Jaden_Lib") (part "RES-0603"))
    )
    (comp (ref "R89")
      (value "NC")
      (footprint "RES-0603")
      (description "Chip Resistor 0603(1608)")
      (fields (field (name "TOLERANCE") "1%") (field (name "MANUFACTURER") "Yageo"))
      (libsource (lib "Jaden_Lib") (part "RES-0603"))
    )
    (comp (ref "R90")
      (value "NC")
      (footprint "RES-0603")
      (description "Chip Resistor 0603(1608)")
      (fields (field (name "TOLERANCE") "1%") (field (name "MANUFACTURER") "Yageo"))
      (libsource (lib "Jaden_Lib") (part "RES-0603"))
    )
    (comp (ref "R91")
      (value "NC")
      (footprint "RES-0603")
      (description "Chip Resistor 0603(1608)")
      (fields (field (name "TOLERANCE") "1%") (field (name "MANUFACTURER") "Yageo"))
      (libsource (lib "Jaden_Lib") (part "RES-0603"))
    )
    (comp (ref "R92")
      (value "NC")
      (footprint "RES-0603")
      (description "Chip Resistor 0603(1608)")
      (fields (field (name "TOLERANCE") "1%") (field (name "MANUFACTURER") "Yageo"))
      (libsource (lib "Jaden_Lib") (part "RES-0603"))
    )
    (comp (ref "R93")
      (value "100K")
      (footprint "RES-0603")
      (description "Chip Resistor 0603(1608)")
      (fields (field (name "TOLERANCE") "1%") (field (name "MANUFACTURER") "Yageo"))
      (libsource (lib "Jaden_Lib") (part "RES-0603"))
    )
    (comp (ref "R94")
      (value "1K")
      (footprint "RES-0603")
      (description "Chip Resistor 0603(1608)")
      (fields (field (name "TOLERANCE") "1%") (field (name "MANUFACTURER") "Yageo"))
      (libsource (lib "Jaden_Lib") (part "RES-0603"))
    )
    (comp (ref "R95")
      (value "1K")
      (footprint "RES-0603")
      (description "Chip Resistor 0603(1608)")
      (fields (field (name "TOLERANCE") "1%") (field (name "MANUFACTURER") "Yageo"))
      (libsource (lib "Jaden_Lib") (part "RES-0603"))
    )
    (comp (ref "R96")
      (value "300R")
      (footprint "RES-0603")
      (description "Chip Resistor 0603(1608)")
      (fields (field (name "TOLERANCE") "1%") (field (name "MANUFACTURER") "Yageo"))
      (libsource (lib "Jaden_Lib") (part "RES-0603"))
    )
    (comp (ref "R97")
      (value "10K")
      (footprint "RES-0603")
      (description "Chip Resistor 0603(1608)")
      (fields (field (name "TOLERANCE") "1%") (field (name "MANUFACTURER") "Yageo"))
      (libsource (lib "Jaden_Lib") (part "RES-0603"))
    )
    (comp (ref "R98")
      (value "NC")
      (footprint "RES-0603")
      (description "Chip Resistor 0603(1608)")
      (fields (field (name "TOLERANCE") "1%") (field (name "MANUFACTURER") "Yageo"))
      (libsource (lib "Jaden_Lib") (part "RES-0603"))
    )
    (comp (ref "R99")
      (value "NC")
      (footprint "RES-0603")
      (description "Chip Resistor 0603(1608)")
      (fields (field (name "TOLERANCE") "1%") (field (name "MANUFACTURER") "Yageo"))
      (libsource (lib "Jaden_Lib") (part "RES-0603"))
    )
    (comp (ref "R100")
      (value "10K")
      (footprint "RES-0603")
      (description "Chip Resistor 0603(1608)")
      (fields (field (name "TOLERANCE") "1%") (field (name "MANUFACTURER") "Yageo"))
      (libsource (lib "Jaden_Lib") (part "RES-0603"))
    )
    (comp (ref "R101")
      (value "300R")
      (footprint "RES-0603")
      (description "Chip Resistor 0603(1608)")
      (fields (field (name "TOLERANCE") "1%") (field (name "MANUFACTURER") "Yageo"))
      (libsource (lib "Jaden_Lib") (part "RES-0603"))
    )
    (comp (ref "R102")
      (value "10K")
      (footprint "RES-0603")
      (description "Chip Resistor 0603(1608)")
      (fields (field (name "TOLERANCE") "1%") (field (name "MANUFACTURER") "Yageo"))
      (libsource (lib "Jaden_Lib") (part "RES-0603"))
    )
    (comp (ref "R103")
      (value "NC")
      (footprint "RES-0603")
      (description "Chip Resistor 0603(1608)")
      (fields (field (name "TOLERANCE") "1%") (field (name "MANUFACTURER") "Yageo"))
      (libsource (lib "Jaden_Lib") (part "RES-0603"))
    )
    (comp (ref "R104")
      (value "10K")
      (footprint "RES-0603")
      (description "Chip Resistor 0603(1608)")
      (fields (field (name "TOLERANCE") "1%") (field (name "MANUFACTURER") "Yageo"))
      (libsource (lib "Jaden_Lib") (part "RES-0603"))
    )
    (comp (ref "R105")
      (value "NC")
      (footprint "RES-0603")
      (description "Chip Resistor 0603(1608)")
      (fields (field (name "TOLERANCE") "1%") (field (name "MANUFACTURER") "Yageo"))
      (libsource (lib "Jaden_Lib") (part "RES-0603"))
    )
    (comp (ref "R106")
      (value "NC")
      (footprint "RES-0603")
      (description "Chip Resistor 0603(1608)")
      (fields (field (name "TOLERANCE") "1%") (field (name "MANUFACTURER") "Yageo"))
      (libsource (lib "Jaden_Lib") (part "RES-0603"))
    )
    (comp (ref "R107")
      (value "NC")
      (footprint "RES-0603")
      (description "Chip Resistor 0603(1608)")
      (fields (field (name "TOLERANCE") "1%") (field (name "MANUFACTURER") "Yageo"))
      (libsource (lib "Jaden_Lib") (part "RES-0603"))
    )
    (comp (ref "R108")
      (value "NC")
      (footprint "RES-0603")
      (description "Chip Resistor 0603(1608)")
      (fields (field (name "TOLERANCE") "1%") (field (name "MANUFACTURER") "Yageo"))
      (libsource (lib "Jaden_Lib") (part "RES-0603"))
    )
    (comp (ref "R109")
      (value "NC")
      (footprint "RES-0603")
      (description "Chip Resistor 0603(1608)")
      (fields (field (name "TOLERANCE") "1%") (field (name "MANUFACTURER") "Yageo"))
      (libsource (lib "Jaden_Lib") (part "RES-0603"))
    )
    (comp (ref "R110")
      (value "NC")
      (footprint "RES-0603")
      (description "Chip Resistor 0603(1608)")
      (fields (field (name "TOLERANCE") "1%") (field (name "MANUFACTURER") "Yageo"))
      (libsource (lib "Jaden_Lib") (part "RES-0603"))
    )
    (comp (ref "R111")
      (value "NC")
      (footprint "RES-0603")
      (description "Chip Resistor 0603(1608)")
      (fields (field (name "TOLERANCE") "1%") (field (name "MANUFACTURER") "Yageo"))
      (libsource (lib "Jaden_Lib") (part "RES-0603"))
    )
    (comp (ref "R112")
      (value "NC")
      (footprint "RES-0603")
      (description "Chip Resistor 0603(1608)")
      (fields (field (name "TOLERANCE") "1%") (field (name "MANUFACTURER") "Yageo"))
      (libsource (lib "Jaden_Lib") (part "RES-0603"))
    )
    (comp (ref "R113")
      (value "NC")
      (footprint "RES-0603")
      (description "Chip Resistor 0603(1608)")
      (fields (field (name "TOLERANCE") "1%") (field (name "MANUFACTURER") "Yageo"))
      (libsource (lib "Jaden_Lib") (part "RES-0603"))
    )
    (comp (ref "SW1")
      (value "ITS-1107(SMD)")
      (footprint "IT-1107(SMD)")
      (description "TACT Switch (SMD)")
      (libsource (lib "Jaden_Lib") (part "ITS-1107(SMD)"))
    )
    (comp (ref "U1")
      (value "LM8805SF5-33V")
      (footprint "SOT-23-5L")
      (description "600mA CMOS LDO Regulator")
      (libsource (lib "Jaden_Lib") (part "LM8805SF5-33V"))
    )
  )
  (nets
    (net (code "1") (name "/I2C1_SCL") (class "Default")
      (node (ref "J1") (pin "9") (pinfunction "9_9") (pintype "passive"))
      (node (ref "J10") (pin "9") (pinfunction "9_9") (pintype "passive"))
      (node (ref "J2") (pin "9") (pinfunction "9_9") (pintype "passive"))
      (node (ref "J3") (pin "9") (pinfunction "9_9") (pintype "passive"))
      (node (ref "J4") (pin "9") (pinfunction "9_9") (pintype "passive"))
      (node (ref "J5") (pin "9") (pinfunction "9_9") (pintype "passive"))
      (node (ref "J6") (pin "9") (pinfunction "9_9") (pintype "passive"))
      (node (ref "J7") (pin "9") (pinfunction "9_9") (pintype "passive"))
      (node (ref "J8") (pin "9") (pinfunction "9_9") (pintype "passive"))
      (node (ref "J9") (pin "9") (pinfunction "9_9") (pintype "passive"))
    )
    (net (code "2") (name "/I2C1_SDA") (class "Default")
      (node (ref "J1") (pin "10") (pinfunction "10_10") (pintype "passive"))
      (node (ref "J10") (pin "10") (pinfunction "10_10") (pintype "passive"))
      (node (ref "J2") (pin "10") (pinfunction "10_10") (pintype "passive"))
      (node (ref "J3") (pin "10") (pinfunction "10_10") (pintype "passive"))
      (node (ref "J4") (pin "10") (pinfunction "10_10") (pintype "passive"))
      (node (ref "J5") (pin "10") (pinfunction "10_10") (pintype "passive"))
      (node (ref "J6") (pin "10") (pinfunction "10_10") (pintype "passive"))
      (node (ref "J7") (pin "10") (pinfunction "10_10") (pintype "passive"))
      (node (ref "J8") (pin "10") (pinfunction "10_10") (pintype "passive"))
      (node (ref "J9") (pin "10") (pinfunction "10_10") (pintype "passive"))
    )
    (net (code "3") (name "/LCD_CS") (class "Default")
      (node (ref "P1") (pin "3") (pinfunction "3_3") (pintype "passive"))
      (node (ref "R91") (pin "1") (pinfunction "1_1") (pintype "passive"))
    )
    (net (code "4") (name "/LCD_DC") (class "Default")
      (node (ref "P1") (pin "5") (pinfunction "5_5") (pintype "passive"))
    )
    (net (code "5") (name "/LCD_LED") (class "Default")
      (node (ref "P1") (pin "8") (pinfunction "8_8") (pintype "passive"))
    )
    (net (code "6") (name "/LCD_MISO") (class "Default")
      (node (ref "P1") (pin "9") (pinfunction "9_9") (pintype "passive"))
    )
    (net (code "7") (name "/LCD_MOSI") (class "Default")
      (node (ref "P1") (pin "6") (pinfunction "6_6") (pintype "passive"))
    )
    (net (code "8") (name "/LCD_RESET") (class "Default")
      (node (ref "P1") (pin "4") (pinfunction "4_4") (pintype "passive"))
      (node (ref "R92") (pin "1") (pinfunction "1_1") (pintype "passive"))
    )
    (net (code "9") (name "/LCD_SCK") (class "Default")
      (node (ref "P1") (pin "7") (pinfunction "7_7") (pintype "passive"))
    )
    (net (code "10") (name "/RST") (class "Default")
      (node (ref "R49") (pin "1") (pinfunction "1_1") (pintype "passive"))
      (node (ref "R5") (pin "1") (pinfunction "1_1") (pintype "passive"))
      (node (ref "R50") (pin "1") (pinfunction "1_1") (pintype "passive"))
      (node (ref "R51") (pin "1") (pinfunction "1_1") (pintype "passive"))
      (node (ref "R52") (pin "1") (pinfunction "1_1") (pintype "passive"))
      (node (ref "R6") (pin "1") (pinfunction "1_1") (pintype "passive"))
      (node (ref "R7") (pin "1") (pinfunction "1_1") (pintype "passive"))
      (node (ref "R8") (pin "1") (pinfunction "1_1") (pintype "passive"))
      (node (ref "R94") (pin "1") (pinfunction "1_1") (pintype "passive"))
      (node (ref "R95") (pin "1") (pinfunction "1_1") (pintype "passive"))
      (node (ref "SW1") (pin "1") (pintype "passive"))
    )
    (net (code "11") (name "5V") (class "Default")
      (node (ref "D1") (pin "1") (pinfunction "A_1") (pintype "passive"))
      (node (ref "D10") (pin "1") (pinfunction "A_1") (pintype "passive"))
      (node (ref "D2") (pin "1") (pinfunction "A_1") (pintype "passive"))
      (node (ref "D3") (pin "1") (pinfunction "A_1") (pintype "passive"))
      (node (ref "D4") (pin "1") (pinfunction "A_1") (pintype "passive"))
      (node (ref "D5") (pin "1") (pinfunction "A_1") (pintype "passive"))
      (node (ref "D6") (pin "1") (pinfunction "A_1") (pintype "passive"))
      (node (ref "D7") (pin "1") (pinfunction "A_1") (pintype "passive"))
      (node (ref "D8") (pin "1") (pinfunction "A_1") (pintype "passive"))
      (node (ref "D9") (pin "1") (pinfunction "A_1") (pintype "passive"))
      (node (ref "R1") (pin "1") (pinfunction "1_1") (pintype "passive"))
      (node (ref "R2") (pin "1") (pinfunction "1_1") (pintype "passive"))
      (node (ref "R3") (pin "1") (pinfunction "1_1") (pintype "passive"))
      (node (ref "R4") (pin "1") (pinfunction "1_1") (pintype "passive"))
      (node (ref "R45") (pin "1") (pinfunction "1_1") (pintype "passive"))
      (node (ref "R46") (pin "1") (pinfunction "1_1") (pintype "passive"))
      (node (ref "R47") (pin "1") (pinfunction "1_1") (pintype "passive"))
      (node (ref "R48") (pin "1") (pinfunction "1_1") (pintype "passive"))
      (node (ref "R89") (pin "1") (pinfunction "1_1") (pintype "passive"))
      (node (ref "R90") (pin "1") (pinfunction "1_1") (pintype "passive"))
    )
    (net (code "12") (name "GND") (class "Default")
      (node (ref "C1") (pin "1") (pinfunction "1_1") (pintype "passive"))
      (node (ref "C2") (pin "1") (pinfunction "1_1") (pintype "passive"))
      (node (ref "C3") (pin "1") (pinfunction "1_1") (pintype "passive"))
      (node (ref "J1") (pin "13") (pinfunction "13_13") (pintype "passive"))
      (node (ref "J1") (pin "18") (pinfunction "18_18") (pintype "passive"))
      (node (ref "J1") (pin "3") (pinfunction "3_3") (pintype "passive"))
      (node (ref "J1") (pin "8") (pinfunction "8_8") (pintype "passive"))
      (node (ref "J10") (pin "13") (pinfunction "13_13") (pintype "passive"))
      (node (ref "J10") (pin "18") (pinfunction "18_18") (pintype "passive"))
      (node (ref "J10") (pin "3") (pinfunction "3_3") (pintype "passive"))
      (node (ref "J10") (pin "8") (pinfunction "8_8") (pintype "passive"))
      (node (ref "J2") (pin "13") (pinfunction "13_13") (pintype "passive"))
      (node (ref "J2") (pin "18") (pinfunction "18_18") (pintype "passive"))
      (node (ref "J2") (pin "3") (pinfunction "3_3") (pintype "passive"))
      (node (ref "J2") (pin "8") (pinfunction "8_8") (pintype "passive"))
      (node (ref "J3") (pin "13") (pinfunction "13_13") (pintype "passive"))
      (node (ref "J3") (pin "18") (pinfunction "18_18") (pintype "passive"))
      (node (ref "J3") (pin "3") (pinfunction "3_3") (pintype "passive"))
      (node (ref "J3") (pin "8") (pinfunction "8_8") (pintype "passive"))
      (node (ref "J4") (pin "13") (pinfunction "13_13") (pintype "passive"))
      (node (ref "J4") (pin "18") (pinfunction "18_18") (pintype "passive"))
      (node (ref "J4") (pin "3") (pinfunction "3_3") (pintype "passive"))
      (node (ref "J4") (pin "8") (pinfunction "8_8") (pintype "passive"))
      (node (ref "J5") (pin "13") (pinfunction "13_13") (pintype "passive"))
      (node (ref "J5") (pin "18") (pinfunction "18_18") (pintype "passive"))
      (node (ref "J5") (pin "3") (pinfunction "3_3") (pintype "passive"))
      (node (ref "J5") (pin "8") (pinfunction "8_8") (pintype "passive"))
      (node (ref "J6") (pin "13") (pinfunction "13_13") (pintype "passive"))
      (node (ref "J6") (pin "18") (pinfunction "18_18") (pintype "passive"))
      (node (ref "J6") (pin "3") (pinfunction "3_3") (pintype "passive"))
      (node (ref "J6") (pin "8") (pinfunction "8_8") (pintype "passive"))
      (node (ref "J7") (pin "13") (pinfunction "13_13") (pintype "passive"))
      (node (ref "J7") (pin "18") (pinfunction "18_18") (pintype "passive"))
      (node (ref "J7") (pin "3") (pinfunction "3_3") (pintype "passive"))
      (node (ref "J7") (pin "8") (pinfunction "8_8") (pintype "passive"))
      (node (ref "J8") (pin "13") (pinfunction "13_13") (pintype "passive"))
      (node (ref "J8") (pin "18") (pinfunction "18_18") (pintype "passive"))
      (node (ref "J8") (pin "3") (pinfunction "3_3") (pintype "passive"))
      (node (ref "J8") (pin "8") (pinfunction "8_8") (pintype "passive"))
      (node (ref "J9") (pin "13") (pinfunction "13_13") (pintype "passive"))
      (node (ref "J9") (pin "18") (pinfunction "18_18") (pintype "passive"))
      (node (ref "J9") (pin "3") (pinfunction "3_3") (pintype "passive"))
      (node (ref "J9") (pin "8") (pinfunction "8_8") (pintype "passive"))
      (node (ref "P1") (pin "2") (pinfunction "2_2") (pintype "passive"))
      (node (ref "R106") (pin "1") (pinfunction "1_1") (pintype "passive"))
      (node (ref "R107") (pin "1") (pinfunction "1_1") (pintype "passive"))
      (node (ref "R108") (pin "1") (pinfunction "1_1") (pintype "passive"))
      (node (ref "R109") (pin "1") (pinfunction "1_1") (pintype "passive"))
      (node (ref "R110") (pin "1") (pinfunction "1_1") (pintype "passive"))
      (node (ref "R111") (pin "1") (pinfunction "1_1") (pintype "passive"))
      (node (ref "R112") (pin "1") (pinfunction "1_1") (pintype "passive"))
      (node (ref "R113") (pin "1") (pinfunction "1_1") (pintype "passive"))
      (node (ref "R29") (pin "1") (pinfunction "1_1") (pintype "passive"))
      (node (ref "R30") (pin "1") (pinfunction "1_1") (pintype "passive"))
      (node (ref "R31") (pin "1") (pinfunction "1_1") (pintype "passive"))
      (node (ref "R32") (pin "1") (pinfunction "1_1") (pintype "passive"))
      (node (ref "R33") (pin "1") (pinfunction "1_1") (pintype "passive"))
      (node (ref "R34") (pin "1") (pinfunction "1_1") (pintype "passive"))
      (node (ref "R35") (pin "1") (pinfunction "1_1") (pintype "passive"))
      (node (ref "R36") (pin "1") (pinfunction "1_1") (pintype "passive"))
      (node (ref "R37") (pin "1") (pinfunction "1_1") (pintype "passive"))
      (node (ref "R38") (pin "1") (pinfunction "1_1") (pintype "passive"))
      (node (ref "R39") (pin "1") (pinfunction "1_1") (pintype "passive"))
      (node (ref "R40") (pin "1") (pinfunction "1_1") (pintype "passive"))
      (node (ref "R41") (pin "1") (pinfunction "1_1") (pintype "passive"))
      (node (ref "R42") (pin "1") (pinfunction "1_1") (pintype "passive"))
      (node (ref "R43") (pin "1") (pinfunction "1_1") (pintype "passive"))
      (node (ref "R44") (pin "1") (pinfunction "1_1") (pintype "passive"))
      (node (ref "R73") (pin "1") (pinfunction "1_1") (pintype "passive"))
      (node (ref "R74") (pin "1") (pinfunction "1_1") (pintype "passive"))
      (node (ref "R75") (pin "1") (pinfunction "1_1") (pintype "passive"))
      (node (ref "R76") (pin "1") (pinfunction "1_1") (pintype "passive"))
      (node (ref "R77") (pin "1") (pinfunction "1_1") (pintype "passive"))
      (node (ref "R78") (pin "1") (pinfunction "1_1") (pintype "passive"))
      (node (ref "R79") (pin "1") (pinfunction "1_1") (pintype "passive"))
      (node (ref "R80") (pin "1") (pinfunction "1_1") (pintype "passive"))
      (node (ref "R81") (pin "1") (pinfunction "1_1") (pintype "passive"))
      (node (ref "R82") (pin "1") (pinfunction "1_1") (pintype "passive"))
      (node (ref "R83") (pin "1") (pinfunction "1_1") (pintype "passive"))
      (node (ref "R84") (pin "1") (pinfunction "1_1") (pintype "passive"))
      (node (ref "R85") (pin "1") (pinfunction "1_1") (pintype "passive"))
      (node (ref "R86") (pin "1") (pinfunction "1_1") (pintype "passive"))
      (node (ref "R87") (pin "1") (pinfunction "1_1") (pintype "passive"))
      (node (ref "R88") (pin "1") (pinfunction "1_1") (pintype "passive"))
      (node (ref "SW1") (pin "2") (pintype "passive"))
      (node (ref "U1") (pin "2") (pinfunction "GND_2") (pintype "power_in"))
    )
    (net (code "13") (name "LCD_3V3") (class "Default")
      (node (ref "C2") (pin "2") (pinfunction "2_2") (pintype "passive"))
      (node (ref "P1") (pin "1") (pinfunction "1_1") (pintype "passive"))
      (node (ref "R91") (pin "2") (pinfunction "2_2") (pintype "passive"))
      (node (ref "R92") (pin "2") (pinfunction "2_2") (pintype "passive"))
      (node (ref "U1") (pin "5") (pinfunction "VOUT_5") (pintype "power_in"))
    )
    (net (code "14") (name "Net-(D1-C)") (class "Default")
      (node (ref "D1") (pin "2") (pinfunction "C_2") (pintype "passive"))
      (node (ref "J1") (pin "2") (pinfunction "2_2") (pintype "passive"))
    )
    (net (code "15") (name "Net-(D2-C)") (class "Default")
      (node (ref "D2") (pin "2") (pinfunction "C_2") (pintype "passive"))
      (node (ref "J2") (pin "2") (pinfunction "2_2") (pintype "passive"))
    )
    (net (code "16") (name "Net-(D3-C)") (class "Default")
      (node (ref "D3") (pin "2") (pinfunction "C_2") (pintype "passive"))
      (node (ref "J3") (pin "2") (pinfunction "2_2") (pintype "passive"))
    )
    (net (code "17") (name "Net-(D4-C)") (class "Default")
      (node (ref "D4") (pin "2") (pinfunction "C_2") (pintype "passive"))
      (node (ref "J4") (pin "2") (pinfunction "2_2") (pintype "passive"))
    )
    (net (code "18") (name "Net-(D5-C)") (class "Default")
      (node (ref "D5") (pin "2") (pinfunction "C_2") (pintype "passive"))
      (node (ref "J5") (pin "2") (pinfunction "2_2") (pintype "passive"))
    )
    (net (code "19") (name "Net-(D6-C)") (class "Default")
      (node (ref "D6") (pin "2") (pinfunction "C_2") (pintype "passive"))
      (node (ref "J6") (pin "2") (pinfunction "2_2") (pintype "passive"))
    )
    (net (code "20") (name "Net-(D7-C)") (class "Default")
      (node (ref "D7") (pin "2") (pinfunction "C_2") (pintype "passive"))
      (node (ref "J7") (pin "2") (pinfunction "2_2") (pintype "passive"))
    )
    (net (code "21") (name "Net-(D8-C)") (class "Default")
      (node (ref "D8") (pin "2") (pinfunction "C_2") (pintype "passive"))
      (node (ref "J8") (pin "2") (pinfunction "2_2") (pintype "passive"))
    )
    (net (code "22") (name "Net-(D9-C)") (class "Default")
      (node (ref "D9") (pin "2") (pinfunction "C_2") (pintype "passive"))
      (node (ref "J9") (pin "2") (pinfunction "2_2") (pintype "passive"))
    )
    (net (code "23") (name "Net-(D10-C)") (class "Default")
      (node (ref "D10") (pin "2") (pinfunction "C_2") (pintype "passive"))
      (node (ref "J10") (pin "2") (pinfunction "2_2") (pintype "passive"))
    )
    (net (code "24") (name "Net-(J1-Pad11)") (class "Default")
      (node (ref "J1") (pin "11") (pinfunction "11_11") (pintype "passive"))
      (node (ref "R5") (pin "2") (pinfunction "2_2") (pintype "passive"))
    )
    (net (code "25") (name "Net-(J1-Pad15)") (class "Default")
      (node (ref "J1") (pin "15") (pinfunction "15_15") (pintype "passive"))
      (node (ref "R9") (pin "2") (pinfunction "2_2") (pintype "passive"))
    )
    (net (code "26") (name "Net-(J1-Pad16)") (class "Default")
      (node (ref "J1") (pin "16") (pinfunction "16_16") (pintype "passive"))
      (node (ref "R13") (pin "1") (pinfunction "1_1") (pintype "passive"))
      (node (ref "R32") (pin "2") (pinfunction "2_2") (pintype "passive"))
    )
    (net (code "27") (name "Net-(J1-Pad17)") (class "Default")
      (node (ref "J1") (pin "17") (pinfunction "17_17") (pintype "passive"))
      (node (ref "R12") (pin "1") (pinfunction "1_1") (pintype "passive"))
      (node (ref "R31") (pin "2") (pinfunction "2_2") (pintype "passive"))
    )
    (net (code "28") (name "Net-(J1-Pad19)") (class "Default")
      (node (ref "J1") (pin "19") (pinfunction "19_19") (pintype "passive"))
      (node (ref "R11") (pin "1") (pinfunction "1_1") (pintype "passive"))
      (node (ref "R30") (pin "2") (pinfunction "2_2") (pintype "passive"))
    )
    (net (code "29") (name "Net-(J1-Pad20)") (class "Default")
      (node (ref "J1") (pin "20") (pinfunction "20_20") (pintype "passive"))
      (node (ref "R10") (pin "1") (pinfunction "1_1") (pintype "passive"))
      (node (ref "R29") (pin "2") (pinfunction "2_2") (pintype "passive"))
    )
    (net (code "30") (name "Net-(J2-Pad11)") (class "Default")
      (node (ref "J2") (pin "11") (pinfunction "11_11") (pintype "passive"))
      (node (ref "R6") (pin "2") (pinfunction "2_2") (pintype "passive"))
    )
    (net (code "31") (name "Net-(J2-Pad15)") (class "Default")
      (node (ref "J2") (pin "15") (pinfunction "15_15") (pintype "passive"))
      (node (ref "R14") (pin "2") (pinfunction "2_2") (pintype "passive"))
    )
    (net (code "32") (name "Net-(J2-Pad16)") (class "Default")
      (node (ref "J2") (pin "16") (pinfunction "16_16") (pintype "passive"))
      (node (ref "R18") (pin "1") (pinfunction "1_1") (pintype "passive"))
      (node (ref "R36") (pin "2") (pinfunction "2_2") (pintype "passive"))
    )
    (net (code "33") (name "Net-(J2-Pad17)") (class "Default")
      (node (ref "J2") (pin "17") (pinfunction "17_17") (pintype "passive"))
      (node (ref "R17") (pin "1") (pinfunction "1_1") (pintype "passive"))
      (node (ref "R35") (pin "2") (pinfunction "2_2") (pintype "passive"))
    )
    (net (code "34") (name "Net-(J2-Pad19)") (class "Default")
      (node (ref "J2") (pin "19") (pinfunction "19_19") (pintype "passive"))
      (node (ref "R16") (pin "1") (pinfunction "1_1") (pintype "passive"))
      (node (ref "R34") (pin "2") (pinfunction "2_2") (pintype "passive"))
    )
    (net (code "35") (name "Net-(J2-Pad20)") (class "Default")
      (node (ref "J2") (pin "20") (pinfunction "20_20") (pintype "passive"))
      (node (ref "R15") (pin "1") (pinfunction "1_1") (pintype "passive"))
      (node (ref "R33") (pin "2") (pinfunction "2_2") (pintype "passive"))
    )
    (net (code "36") (name "Net-(J3-Pad11)") (class "Default")
      (node (ref "J3") (pin "11") (pinfunction "11_11") (pintype "passive"))
      (node (ref "R7") (pin "2") (pinfunction "2_2") (pintype "passive"))
    )
    (net (code "37") (name "Net-(J3-Pad15)") (class "Default")
      (node (ref "J3") (pin "15") (pinfunction "15_15") (pintype "passive"))
      (node (ref "R19") (pin "2") (pinfunction "2_2") (pintype "passive"))
    )
    (net (code "38") (name "Net-(J3-Pad16)") (class "Default")
      (node (ref "J3") (pin "16") (pinfunction "16_16") (pintype "passive"))
      (node (ref "R23") (pin "1") (pinfunction "1_1") (pintype "passive"))
      (node (ref "R40") (pin "2") (pinfunction "2_2") (pintype "passive"))
    )
    (net (code "39") (name "Net-(J3-Pad17)") (class "Default")
      (node (ref "J3") (pin "17") (pinfunction "17_17") (pintype "passive"))
      (node (ref "R22") (pin "1") (pinfunction "1_1") (pintype "passive"))
      (node (ref "R39") (pin "2") (pinfunction "2_2") (pintype "passive"))
    )
    (net (code "40") (name "Net-(J3-Pad19)") (class "Default")
      (node (ref "J3") (pin "19") (pinfunction "19_19") (pintype "passive"))
      (node (ref "R21") (pin "1") (pinfunction "1_1") (pintype "passive"))
      (node (ref "R38") (pin "2") (pinfunction "2_2") (pintype "passive"))
    )
    (net (code "41") (name "Net-(J3-Pad20)") (class "Default")
      (node (ref "J3") (pin "20") (pinfunction "20_20") (pintype "passive"))
      (node (ref "R20") (pin "1") (pinfunction "1_1") (pintype "passive"))
      (node (ref "R37") (pin "2") (pinfunction "2_2") (pintype "passive"))
    )
    (net (code "42") (name "Net-(J4-Pad11)") (class "Default")
      (node (ref "J4") (pin "11") (pinfunction "11_11") (pintype "passive"))
      (node (ref "R8") (pin "2") (pinfunction "2_2") (pintype "passive"))
    )
    (net (code "43") (name "Net-(J4-Pad15)") (class "Default")
      (node (ref "J4") (pin "15") (pinfunction "15_15") (pintype "passive"))
      (node (ref "R24") (pin "2") (pinfunction "2_2") (pintype "passive"))
    )
    (net (code "44") (name "Net-(J4-Pad16)") (class "Default")
      (node (ref "J4") (pin "16") (pinfunction "16_16") (pintype "passive"))
      (node (ref "R28") (pin "1") (pinfunction "1_1") (pintype "passive"))
      (node (ref "R44") (pin "2") (pinfunction "2_2") (pintype "passive"))
    )
    (net (code "45") (name "Net-(J4-Pad17)") (class "Default")
      (node (ref "J4") (pin "17") (pinfunction "17_17") (pintype "passive"))
      (node (ref "R27") (pin "1") (pinfunction "1_1") (pintype "passive"))
      (node (ref "R43") (pin "2") (pinfunction "2_2") (pintype "passive"))
    )
    (net (code "46") (name "Net-(J4-Pad19)") (class "Default")
      (node (ref "J4") (pin "19") (pinfunction "19_19") (pintype "passive"))
      (node (ref "R26") (pin "1") (pinfunction "1_1") (pintype "passive"))
      (node (ref "R42") (pin "2") (pinfunction "2_2") (pintype "passive"))
    )
    (net (code "47") (name "Net-(J4-Pad20)") (class "Default")
      (node (ref "J4") (pin "20") (pinfunction "20_20") (pintype "passive"))
      (node (ref "R25") (pin "1") (pinfunction "1_1") (pintype "passive"))
      (node (ref "R41") (pin "2") (pinfunction "2_2") (pintype "passive"))
    )
    (net (code "48") (name "Net-(J5-Pad11)") (class "Default")
      (node (ref "J5") (pin "11") (pinfunction "11_11") (pintype "passive"))
      (node (ref "R49") (pin "2") (pinfunction "2_2") (pintype "passive"))
    )
    (net (code "49") (name "Net-(J5-Pad15)") (class "Default")
      (node (ref "J5") (pin "15") (pinfunction "15_15") (pintype "passive"))
      (node (ref "R53") (pin "2") (pinfunction "2_2") (pintype "passive"))
    )
    (net (code "50") (name "Net-(J5-Pad16)") (class "Default")
      (node (ref "J5") (pin "16") (pinfunction "16_16") (pintype "passive"))
      (node (ref "R57") (pin "1") (pinfunction "1_1") (pintype "passive"))
      (node (ref "R76") (pin "2") (pinfunction "2_2") (pintype "passive"))
    )
    (net (code "51") (name "Net-(J5-Pad17)") (class "Default")
      (node (ref "J5") (pin "17") (pinfunction "17_17") (pintype "passive"))
      (node (ref "R56") (pin "1") (pinfunction "1_1") (pintype "passive"))
      (node (ref "R75") (pin "2") (pinfunction "2_2") (pintype "passive"))
    )
    (net (code "52") (name "Net-(J5-Pad19)") (class "Default")
      (node (ref "J5") (pin "19") (pinfunction "19_19") (pintype "passive"))
      (node (ref "R55") (pin "1") (pinfunction "1_1") (pintype "passive"))
      (node (ref "R74") (pin "2") (pinfunction "2_2") (pintype "passive"))
    )
    (net (code "53") (name "Net-(J5-Pad20)") (class "Default")
      (node (ref "J5") (pin "20") (pinfunction "20_20") (pintype "passive"))
      (node (ref "R54") (pin "1") (pinfunction "1_1") (pintype "passive"))
      (node (ref "R73") (pin "2") (pinfunction "2_2") (pintype "passive"))
    )
    (net (code "54") (name "Net-(J6-Pad11)") (class "Default")
      (node (ref "J6") (pin "11") (pinfunction "11_11") (pintype "passive"))
      (node (ref "R50") (pin "2") (pinfunction "2_2") (pintype "passive"))
    )
    (net (code "55") (name "Net-(J6-Pad15)") (class "Default")
      (node (ref "J6") (pin "15") (pinfunction "15_15") (pintype "passive"))
      (node (ref "R58") (pin "2") (pinfunction "2_2") (pintype "passive"))
    )
    (net (code "56") (name "Net-(J6-Pad16)") (class "Default")
      (node (ref "J6") (pin "16") (pinfunction "16_16") (pintype "passive"))
      (node (ref "R62") (pin "1") (pinfunction "1_1") (pintype "passive"))
      (node (ref "R80") (pin "2") (pinfunction "2_2") (pintype "passive"))
    )
    (net (code "57") (name "Net-(J6-Pad17)") (class "Default")
      (node (ref "J6") (pin "17") (pinfunction "17_17") (pintype "passive"))
      (node (ref "R61") (pin "1") (pinfunction "1_1") (pintype "passive"))
      (node (ref "R79") (pin "2") (pinfunction "2_2") (pintype "passive"))
    )
    (net (code "58") (name "Net-(J6-Pad19)") (class "Default")
      (node (ref "J6") (pin "19") (pinfunction "19_19") (pintype "passive"))
      (node (ref "R60") (pin "1") (pinfunction "1_1") (pintype "passive"))
      (node (ref "R78") (pin "2") (pinfunction "2_2") (pintype "passive"))
    )
    (net (code "59") (name "Net-(J6-Pad20)") (class "Default")
      (node (ref "J6") (pin "20") (pinfunction "20_20") (pintype "passive"))
      (node (ref "R59") (pin "1") (pinfunction "1_1") (pintype "passive"))
      (node (ref "R77") (pin "2") (pinfunction "2_2") (pintype "passive"))
    )
    (net (code "60") (name "Net-(J7-Pad11)") (class "Default")
      (node (ref "J7") (pin "11") (pinfunction "11_11") (pintype "passive"))
      (node (ref "R51") (pin "2") (pinfunction "2_2") (pintype "passive"))
    )
    (net (code "61") (name "Net-(J7-Pad15)") (class "Default")
      (node (ref "J7") (pin "15") (pinfunction "15_15") (pintype "passive"))
      (node (ref "R63") (pin "2") (pinfunction "2_2") (pintype "passive"))
    )
    (net (code "62") (name "Net-(J7-Pad16)") (class "Default")
      (node (ref "J7") (pin "16") (pinfunction "16_16") (pintype "passive"))
      (node (ref "R67") (pin "1") (pinfunction "1_1") (pintype "passive"))
      (node (ref "R84") (pin "2") (pinfunction "2_2") (pintype "passive"))
    )
    (net (code "63") (name "Net-(J7-Pad17)") (class "Default")
      (node (ref "J7") (pin "17") (pinfunction "17_17") (pintype "passive"))
      (node (ref "R66") (pin "1") (pinfunction "1_1") (pintype "passive"))
      (node (ref "R83") (pin "2") (pinfunction "2_2") (pintype "passive"))
    )
    (net (code "64") (name "Net-(J7-Pad19)") (class "Default")
      (node (ref "J7") (pin "19") (pinfunction "19_19") (pintype "passive"))
      (node (ref "R65") (pin "1") (pinfunction "1_1") (pintype "passive"))
      (node (ref "R82") (pin "2") (pinfunction "2_2") (pintype "passive"))
    )
    (net (code "65") (name "Net-(J7-Pad20)") (class "Default")
      (node (ref "J7") (pin "20") (pinfunction "20_20") (pintype "passive"))
      (node (ref "R64") (pin "1") (pinfunction "1_1") (pintype "passive"))
      (node (ref "R81") (pin "2") (pinfunction "2_2") (pintype "passive"))
    )
    (net (code "66") (name "Net-(J8-Pad11)") (class "Default")
      (node (ref "J8") (pin "11") (pinfunction "11_11") (pintype "passive"))
      (node (ref "R52") (pin "2") (pinfunction "2_2") (pintype "passive"))
    )
    (net (code "67") (name "Net-(J8-Pad15)") (class "Default")
      (node (ref "J8") (pin "15") (pinfunction "15_15") (pintype "passive"))
      (node (ref "R68") (pin "2") (pinfunction "2_2") (pintype "passive"))
    )
    (net (code "68") (name "Net-(J8-Pad16)") (class "Default")
      (node (ref "J8") (pin "16") (pinfunction "16_16") (pintype "passive"))
      (node (ref "R72") (pin "1") (pinfunction "1_1") (pintype "passive"))
      (node (ref "R88") (pin "2") (pinfunction "2_2") (pintype "passive"))
    )
    (net (code "69") (name "Net-(J8-Pad17)") (class "Default")
      (node (ref "J8") (pin "17") (pinfunction "17_17") (pintype "passive"))
      (node (ref "R71") (pin "1") (pinfunction "1_1") (pintype "passive"))
      (node (ref "R87") (pin "2") (pinfunction "2_2") (pintype "passive"))
    )
    (net (code "70") (name "Net-(J8-Pad19)") (class "Default")
      (node (ref "J8") (pin "19") (pinfunction "19_19") (pintype "passive"))
      (node (ref "R70") (pin "1") (pinfunction "1_1") (pintype "passive"))
      (node (ref "R86") (pin "2") (pinfunction "2_2") (pintype "passive"))
    )
    (net (code "71") (name "Net-(J8-Pad20)") (class "Default")
      (node (ref "J8") (pin "20") (pinfunction "20_20") (pintype "passive"))
      (node (ref "R69") (pin "1") (pinfunction "1_1") (pintype "passive"))
      (node (ref "R85") (pin "2") (pinfunction "2_2") (pintype "passive"))
    )
    (net (code "72") (name "Net-(J9-Pad11)") (class "Default")
      (node (ref "J9") (pin "11") (pinfunction "11_11") (pintype "passive"))
      (node (ref "R94") (pin "2") (pinfunction "2_2") (pintype "passive"))
    )
    (net (code "73") (name "Net-(J9-Pad15)") (class "Default")
      (node (ref "J9") (pin "15") (pinfunction "15_15") (pintype "passive"))
      (node (ref "R96") (pin "2") (pinfunction "2_2") (pintype "passive"))
    )
    (net (code "74") (name "Net-(J9-Pad16)") (class "Default")
      (node (ref "J9") (pin "16") (pinfunction "16_16") (pintype "passive"))
      (node (ref "R100") (pin "1") (pinfunction "1_1") (pintype "passive"))
      (node (ref "R109") (pin "2") (pinfunction "2_2") (pintype "passive"))
    )
    (net (code "75") (name "Net-(J9-Pad17)") (class "Default")
      (node (ref "J9") (pin "17") (pinfunction "17_17") (pintype "passive"))
      (node (ref "R108") (pin "2") (pinfunction "2_2") (pintype "passive"))
      (node (ref "R99") (pin "1") (pinfunction "1_1") (pintype "passive"))
    )
    (net (code "76") (name "Net-(J9-Pad19)") (class "Default")
      (node (ref "J9") (pin "19") (pinfunction "19_19") (pintype "passive"))
      (node (ref "R107") (pin "2") (pinfunction "2_2") (pintype "passive"))
      (node (ref "R98") (pin "1") (pinfunction "1_1") (pintype "passive"))
    )
    (net (code "77") (name "Net-(J9-Pad20)") (class "Default")
      (node (ref "J9") (pin "20") (pinfunction "20_20") (pintype "passive"))
      (node (ref "R106") (pin "2") (pinfunction "2_2") (pintype "passive"))
      (node (ref "R97") (pin "1") (pinfunction "1_1") (pintype "passive"))
    )
    (net (code "78") (name "Net-(J10-Pad11)") (class "Default")
      (node (ref "J10") (pin "11") (pinfunction "11_11") (pintype "passive"))
      (node (ref "R95") (pin "2") (pinfunction "2_2") (pintype "passive"))
    )
    (net (code "79") (name "Net-(J10-Pad15)") (class "Default")
      (node (ref "J10") (pin "15") (pinfunction "15_15") (pintype "passive"))
      (node (ref "R101") (pin "2") (pinfunction "2_2") (pintype "passive"))
    )
    (net (code "80") (name "Net-(J10-Pad16)") (class "Default")
      (node (ref "J10") (pin "16") (pinfunction "16_16") (pintype "passive"))
      (node (ref "R105") (pin "1") (pinfunction "1_1") (pintype "passive"))
      (node (ref "R113") (pin "2") (pinfunction "2_2") (pintype "passive"))
    )
    (net (code "81") (name "Net-(J10-Pad17)") (class "Default")
      (node (ref "J10") (pin "17") (pinfunction "17_17") (pintype "passive"))
      (node (ref "R104") (pin "1") (pinfunction "1_1") (pintype "passive"))
      (node (ref "R112") (pin "2") (pinfunction "2_2") (pintype "passive"))
    )
    (net (code "82") (name "Net-(J10-Pad19)") (class "Default")
      (node (ref "J10") (pin "19") (pinfunction "19_19") (pintype "passive"))
      (node (ref "R103") (pin "1") (pinfunction "1_1") (pintype "passive"))
      (node (ref "R111") (pin "2") (pinfunction "2_2") (pintype "passive"))
    )
    (net (code "83") (name "Net-(J10-Pad20)") (class "Default")
      (node (ref "J10") (pin "20") (pinfunction "20_20") (pintype "passive"))
      (node (ref "R102") (pin "1") (pinfunction "1_1") (pintype "passive"))
      (node (ref "R110") (pin "2") (pinfunction "2_2") (pintype "passive"))
    )
    (net (code "84") (name "Net-(LD1-A)") (class "Default")
      (node (ref "J1") (pin "5") (pinfunction "5_5") (pintype "passive"))
      (node (ref "LD1") (pin "1") (pinfunction "A_1") (pintype "passive"))
      (node (ref "R10") (pin "2") (pinfunction "2_2") (pintype "passive"))
      (node (ref "R11") (pin "2") (pinfunction "2_2") (pintype "passive"))
      (node (ref "R12") (pin "2") (pinfunction "2_2") (pintype "passive"))
      (node (ref "R13") (pin "2") (pinfunction "2_2") (pintype "passive"))
    )
    (net (code "85") (name "Net-(LD1-K)") (class "Default")
      (node (ref "LD1") (pin "2") (pinfunction "K_2") (pintype "passive"))
      (node (ref "R9") (pin "1") (pinfunction "1_1") (pintype "passive"))
    )
    (net (code "86") (name "Net-(LD2-A)") (class "Default")
      (node (ref "J2") (pin "5") (pinfunction "5_5") (pintype "passive"))
      (node (ref "LD2") (pin "1") (pinfunction "A_1") (pintype "passive"))
      (node (ref "R15") (pin "2") (pinfunction "2_2") (pintype "passive"))
      (node (ref "R16") (pin "2") (pinfunction "2_2") (pintype "passive"))
      (node (ref "R17") (pin "2") (pinfunction "2_2") (pintype "passive"))
      (node (ref "R18") (pin "2") (pinfunction "2_2") (pintype "passive"))
    )
    (net (code "87") (name "Net-(LD2-K)") (class "Default")
      (node (ref "LD2") (pin "2") (pinfunction "K_2") (pintype "passive"))
      (node (ref "R14") (pin "1") (pinfunction "1_1") (pintype "passive"))
    )
    (net (code "88") (name "Net-(LD3-A)") (class "Default")
      (node (ref "J3") (pin "5") (pinfunction "5_5") (pintype "passive"))
      (node (ref "LD3") (pin "1") (pinfunction "A_1") (pintype "passive"))
      (node (ref "R20") (pin "2") (pinfunction "2_2") (pintype "passive"))
      (node (ref "R21") (pin "2") (pinfunction "2_2") (pintype "passive"))
      (node (ref "R22") (pin "2") (pinfunction "2_2") (pintype "passive"))
      (node (ref "R23") (pin "2") (pinfunction "2_2") (pintype "passive"))
    )
    (net (code "89") (name "Net-(LD3-K)") (class "Default")
      (node (ref "LD3") (pin "2") (pinfunction "K_2") (pintype "passive"))
      (node (ref "R19") (pin "1") (pinfunction "1_1") (pintype "passive"))
    )
    (net (code "90") (name "Net-(LD4-A)") (class "Default")
      (node (ref "J4") (pin "5") (pinfunction "5_5") (pintype "passive"))
      (node (ref "LD4") (pin "1") (pinfunction "A_1") (pintype "passive"))
      (node (ref "R25") (pin "2") (pinfunction "2_2") (pintype "passive"))
      (node (ref "R26") (pin "2") (pinfunction "2_2") (pintype "passive"))
      (node (ref "R27") (pin "2") (pinfunction "2_2") (pintype "passive"))
      (node (ref "R28") (pin "2") (pinfunction "2_2") (pintype "passive"))
    )
    (net (code "91") (name "Net-(LD4-K)") (class "Default")
      (node (ref "LD4") (pin "2") (pinfunction "K_2") (pintype "passive"))
      (node (ref "R24") (pin "1") (pinfunction "1_1") (pintype "passive"))
    )
    (net (code "92") (name "Net-(LD5-A)") (class "Default")
      (node (ref "J5") (pin "5") (pinfunction "5_5") (pintype "passive"))
      (node (ref "LD5") (pin "1") (pinfunction "A_1") (pintype "passive"))
      (node (ref "R54") (pin "2") (pinfunction "2_2") (pintype "passive"))
      (node (ref "R55") (pin "2") (pinfunction "2_2") (pintype "passive"))
      (node (ref "R56") (pin "2") (pinfunction "2_2") (pintype "passive"))
      (node (ref "R57") (pin "2") (pinfunction "2_2") (pintype "passive"))
    )
    (net (code "93") (name "Net-(LD5-K)") (class "Default")
      (node (ref "LD5") (pin "2") (pinfunction "K_2") (pintype "passive"))
      (node (ref "R53") (pin "1") (pinfunction "1_1") (pintype "passive"))
    )
    (net (code "94") (name "Net-(LD6-A)") (class "Default")
      (node (ref "J6") (pin "5") (pinfunction "5_5") (pintype "passive"))
      (node (ref "LD6") (pin "1") (pinfunction "A_1") (pintype "passive"))
      (node (ref "R59") (pin "2") (pinfunction "2_2") (pintype "passive"))
      (node (ref "R60") (pin "2") (pinfunction "2_2") (pintype "passive"))
      (node (ref "R61") (pin "2") (pinfunction "2_2") (pintype "passive"))
      (node (ref "R62") (pin "2") (pinfunction "2_2") (pintype "passive"))
    )
    (net (code "95") (name "Net-(LD6-K)") (class "Default")
      (node (ref "LD6") (pin "2") (pinfunction "K_2") (pintype "passive"))
      (node (ref "R58") (pin "1") (pinfunction "1_1") (pintype "passive"))
    )
    (net (code "96") (name "Net-(LD7-A)") (class "Default")
      (node (ref "J7") (pin "5") (pinfunction "5_5") (pintype "passive"))
      (node (ref "LD7") (pin "1") (pinfunction "A_1") (pintype "passive"))
      (node (ref "R64") (pin "2") (pinfunction "2_2") (pintype "passive"))
      (node (ref "R65") (pin "2") (pinfunction "2_2") (pintype "passive"))
      (node (ref "R66") (pin "2") (pinfunction "2_2") (pintype "passive"))
      (node (ref "R67") (pin "2") (pinfunction "2_2") (pintype "passive"))
    )
    (net (code "97") (name "Net-(LD7-K)") (class "Default")
      (node (ref "LD7") (pin "2") (pinfunction "K_2") (pintype "passive"))
      (node (ref "R63") (pin "1") (pinfunction "1_1") (pintype "passive"))
    )
    (net (code "98") (name "Net-(LD8-A)") (class "Default")
      (node (ref "J8") (pin "5") (pinfunction "5_5") (pintype "passive"))
      (node (ref "LD8") (pin "1") (pinfunction "A_1") (pintype "passive"))
      (node (ref "R69") (pin "2") (pinfunction "2_2") (pintype "passive"))
      (node (ref "R70") (pin "2") (pinfunction "2_2") (pintype "passive"))
      (node (ref "R71") (pin "2") (pinfunction "2_2") (pintype "passive"))
      (node (ref "R72") (pin "2") (pinfunction "2_2") (pintype "passive"))
    )
    (net (code "99") (name "Net-(LD8-K)") (class "Default")
      (node (ref "LD8") (pin "2") (pinfunction "K_2") (pintype "passive"))
      (node (ref "R68") (pin "1") (pinfunction "1_1") (pintype "passive"))
    )
    (net (code "100") (name "Net-(LD9-A)") (class "Default")
      (node (ref "J9") (pin "5") (pinfunction "5_5") (pintype "passive"))
      (node (ref "LD9") (pin "1") (pinfunction "A_1") (pintype "passive"))
      (node (ref "R100") (pin "2") (pinfunction "2_2") (pintype "passive"))
      (node (ref "R97") (pin "2") (pinfunction "2_2") (pintype "passive"))
      (node (ref "R98") (pin "2") (pinfunction "2_2") (pintype "passive"))
      (node (ref "R99") (pin "2") (pinfunction "2_2") (pintype "passive"))
    )
    (net (code "101") (name "Net-(LD9-K)") (class "Default")
      (node (ref "LD9") (pin "2") (pinfunction "K_2") (pintype "passive"))
      (node (ref "R96") (pin "1") (pinfunction "1_1") (pintype "passive"))
    )
    (net (code "102") (name "Net-(LD10-A)") (class "Default")
      (node (ref "J10") (pin "5") (pinfunction "5_5") (pintype "passive"))
      (node (ref "LD10") (pin "1") (pinfunction "A_1") (pintype "passive"))
      (node (ref "R102") (pin "2") (pinfunction "2_2") (pintype "passive"))
      (node (ref "R103") (pin "2") (pinfunction "2_2") (pintype "passive"))
      (node (ref "R104") (pin "2") (pinfunction "2_2") (pintype "passive"))
      (node (ref "R105") (pin "2") (pinfunction "2_2") (pintype "passive"))
    )
    (net (code "103") (name "Net-(LD10-K)") (class "Default")
      (node (ref "LD10") (pin "2") (pinfunction "K_2") (pintype "passive"))
      (node (ref "R101") (pin "1") (pinfunction "1_1") (pintype "passive"))
    )
    (net (code "104") (name "Net-(U1-BYP)") (class "Default")
      (node (ref "C3") (pin "2") (pinfunction "2_2") (pintype "passive"))
      (node (ref "U1") (pin "4") (pinfunction "BYP_4") (pintype "power_in"))
    )
    (net (code "105") (name "Net-(U1-EN)") (class "Default")
      (node (ref "R93") (pin "2") (pinfunction "2_2") (pintype "passive"))
      (node (ref "U1") (pin "3") (pinfunction "EN_3") (pintype "power_in"))
    )
    (net (code "106") (name "VBUS") (class "Default")
      (node (ref "J1") (pin "1") (pinfunction "1_1") (pintype "passive"))
      (node (ref "J10") (pin "1") (pinfunction "1_1") (pintype "passive"))
      (node (ref "J2") (pin "1") (pinfunction "1_1") (pintype "passive"))
      (node (ref "J3") (pin "1") (pinfunction "1_1") (pintype "passive"))
      (node (ref "J4") (pin "1") (pinfunction "1_1") (pintype "passive"))
      (node (ref "J5") (pin "1") (pinfunction "1_1") (pintype "passive"))
      (node (ref "J6") (pin "1") (pinfunction "1_1") (pintype "passive"))
      (node (ref "J7") (pin "1") (pinfunction "1_1") (pintype "passive"))
      (node (ref "J8") (pin "1") (pinfunction "1_1") (pintype "passive"))
      (node (ref "J9") (pin "1") (pinfunction "1_1") (pintype "passive"))
      (node (ref "R1") (pin "2") (pinfunction "2_2") (pintype "passive"))
      (node (ref "R2") (pin "2") (pinfunction "2_2") (pintype "passive"))
      (node (ref "R3") (pin "2") (pinfunction "2_2") (pintype "passive"))
      (node (ref "R4") (pin "2") (pinfunction "2_2") (pintype "passive"))
      (node (ref "R45") (pin "2") (pinfunction "2_2") (pintype "passive"))
      (node (ref "R46") (pin "2") (pinfunction "2_2") (pintype "passive"))
      (node (ref "R47") (pin "2") (pinfunction "2_2") (pintype "passive"))
      (node (ref "R48") (pin "2") (pinfunction "2_2") (pintype "passive"))
      (node (ref "R89") (pin "2") (pinfunction "2_2") (pintype "passive"))
      (node (ref "R90") (pin "2") (pinfunction "2_2") (pintype "passive"))
    )
    (net (code "107") (name "VSYS") (class "Default")
      (node (ref "C1") (pin "2") (pinfunction "2_2") (pintype "passive"))
      (node (ref "R93") (pin "1") (pinfunction "1_1") (pintype "passive"))
      (node (ref "U1") (pin "1") (pinfunction "IN_1") (pintype "power_in"))
    )
    (net (code "108") (name "unconnected-(J1-Pad4)") (class "Default")
      (node (ref "J1") (pin "4") (pinfunction "4_4") (pintype "passive+no_connect"))
    )
    (net (code "109") (name "unconnected-(J1-Pad6)") (class "Default")
      (node (ref "J1") (pin "6") (pinfunction "6_6") (pintype "passive+no_connect"))
    )
    (net (code "110") (name "unconnected-(J1-Pad7)") (class "Default")
      (node (ref "J1") (pin "7") (pinfunction "7_7") (pintype "passive+no_connect"))
    )
    (net (code "111") (name "unconnected-(J1-Pad12)") (class "Default")
      (node (ref "J1") (pin "12") (pinfunction "12_12") (pintype "passive+no_connect"))
    )
    (net (code "112") (name "unconnected-(J1-Pad14)") (class "Default")
      (node (ref "J1") (pin "14") (pinfunction "14_14") (pintype "passive+no_connect"))
    )
    (net (code "113") (name "unconnected-(J2-Pad4)") (class "Default")
      (node (ref "J2") (pin "4") (pinfunction "4_4") (pintype "passive+no_connect"))
    )
    (net (code "114") (name "unconnected-(J2-Pad6)") (class "Default")
      (node (ref "J2") (pin "6") (pinfunction "6_6") (pintype "passive+no_connect"))
    )
    (net (code "115") (name "unconnected-(J2-Pad7)") (class "Default")
      (node (ref "J2") (pin "7") (pinfunction "7_7") (pintype "passive+no_connect"))
    )
    (net (code "116") (name "unconnected-(J2-Pad12)") (class "Default")
      (node (ref "J2") (pin "12") (pinfunction "12_12") (pintype "passive+no_connect"))
    )
    (net (code "117") (name "unconnected-(J2-Pad14)") (class "Default")
      (node (ref "J2") (pin "14") (pinfunction "14_14") (pintype "passive+no_connect"))
    )
    (net (code "118") (name "unconnected-(J3-Pad4)") (class "Default")
      (node (ref "J3") (pin "4") (pinfunction "4_4") (pintype "passive+no_connect"))
    )
    (net (code "119") (name "unconnected-(J3-Pad6)") (class "Default")
      (node (ref "J3") (pin "6") (pinfunction "6_6") (pintype "passive+no_connect"))
    )
    (net (code "120") (name "unconnected-(J3-Pad7)") (class "Default")
      (node (ref "J3") (pin "7") (pinfunction "7_7") (pintype "passive+no_connect"))
    )
    (net (code "121") (name "unconnected-(J3-Pad12)") (class "Default")
      (node (ref "J3") (pin "12") (pinfunction "12_12") (pintype "passive+no_connect"))
    )
    (net (code "122") (name "unconnected-(J3-Pad14)") (class "Default")
      (node (ref "J3") (pin "14") (pinfunction "14_14") (pintype "passive+no_connect"))
    )
    (net (code "123") (name "unconnected-(J4-Pad4)") (class "Default")
      (node (ref "J4") (pin "4") (pinfunction "4_4") (pintype "passive+no_connect"))
    )
    (net (code "124") (name "unconnected-(J4-Pad6)") (class "Default")
      (node (ref "J4") (pin "6") (pinfunction "6_6") (pintype "passive+no_connect"))
    )
    (net (code "125") (name "unconnected-(J4-Pad7)") (class "Default")
      (node (ref "J4") (pin "7") (pinfunction "7_7") (pintype "passive+no_connect"))
    )
    (net (code "126") (name "unconnected-(J4-Pad12)") (class "Default")
      (node (ref "J4") (pin "12") (pinfunction "12_12") (pintype "passive+no_connect"))
    )
    (net (code "127") (name "unconnected-(J4-Pad14)") (class "Default")
      (node (ref "J4") (pin "14") (pinfunction "14_14") (pintype "passive+no_connect"))
    )
    (net (code "128") (name "unconnected-(J5-Pad4)") (class "Default")
      (node (ref "J5") (pin "4") (pinfunction "4_4") (pintype "passive+no_connect"))
    )
    (net (code "129") (name "unconnected-(J5-Pad6)") (class "Default")
      (node (ref "J5") (pin "6") (pinfunction "6_6") (pintype "passive+no_connect"))
    )
    (net (code "130") (name "unconnected-(J5-Pad7)") (class "Default")
      (node (ref "J5") (pin "7") (pinfunction "7_7") (pintype "passive+no_connect"))
    )
    (net (code "131") (name "unconnected-(J5-Pad12)") (class "Default")
      (node (ref "J5") (pin "12") (pinfunction "12_12") (pintype "passive"))
    )
    (net (code "132") (name "unconnected-(J5-Pad14)") (class "Default")
      (node (ref "J5") (pin "14") (pinfunction "14_14") (pintype "passive+no_connect"))
    )
    (net (code "133") (name "unconnected-(J6-Pad4)") (class "Default")
      (node (ref "J6") (pin "4") (pinfunction "4_4") (pintype "passive+no_connect"))
    )
    (net (code "134") (name "unconnected-(J6-Pad6)") (class "Default")
      (node (ref "J6") (pin "6") (pinfunction "6_6") (pintype "passive+no_connect"))
    )
    (net (code "135") (name "unconnected-(J6-Pad7)") (class "Default")
      (node (ref "J6") (pin "7") (pinfunction "7_7") (pintype "passive+no_connect"))
    )
    (net (code "136") (name "unconnected-(J6-Pad12)") (class "Default")
      (node (ref "J6") (pin "12") (pinfunction "12_12") (pintype "passive+no_connect"))
    )
    (net (code "137") (name "unconnected-(J6-Pad14)") (class "Default")
      (node (ref "J6") (pin "14") (pinfunction "14_14") (pintype "passive+no_connect"))
    )
    (net (code "138") (name "unconnected-(J7-Pad4)") (class "Default")
      (node (ref "J7") (pin "4") (pinfunction "4_4") (pintype "passive+no_connect"))
    )
    (net (code "139") (name "unconnected-(J7-Pad6)") (class "Default")
      (node (ref "J7") (pin "6") (pinfunction "6_6") (pintype "passive+no_connect"))
    )
    (net (code "140") (name "unconnected-(J7-Pad7)") (class "Default")
      (node (ref "J7") (pin "7") (pinfunction "7_7") (pintype "passive+no_connect"))
    )
    (net (code "141") (name "unconnected-(J7-Pad12)") (class "Default")
      (node (ref "J7") (pin "12") (pinfunction "12_12") (pintype "passive+no_connect"))
    )
    (net (code "142") (name "unconnected-(J7-Pad14)") (class "Default")
      (node (ref "J7") (pin "14") (pinfunction "14_14") (pintype "passive+no_connect"))
    )
    (net (code "143") (name "unconnected-(J8-Pad4)") (class "Default")
      (node (ref "J8") (pin "4") (pinfunction "4_4") (pintype "passive+no_connect"))
    )
    (net (code "144") (name "unconnected-(J8-Pad6)") (class "Default")
      (node (ref "J8") (pin "6") (pinfunction "6_6") (pintype "passive+no_connect"))
    )
    (net (code "145") (name "unconnected-(J8-Pad7)") (class "Default")
      (node (ref "J8") (pin "7") (pinfunction "7_7") (pintype "passive+no_connect"))
    )
    (net (code "146") (name "unconnected-(J8-Pad12)") (class "Default")
      (node (ref "J8") (pin "12") (pinfunction "12_12") (pintype "passive+no_connect"))
    )
    (net (code "147") (name "unconnected-(J8-Pad14)") (class "Default")
      (node (ref "J8") (pin "14") (pinfunction "14_14") (pintype "passive+no_connect"))
    )
    (net (code "148") (name "unconnected-(J9-Pad4)") (class "Default")
      (node (ref "J9") (pin "4") (pinfunction "4_4") (pintype "passive+no_connect"))
    )
    (net (code "149") (name "unconnected-(J9-Pad6)") (class "Default")
      (node (ref "J9") (pin "6") (pinfunction "6_6") (pintype "passive+no_connect"))
    )
    (net (code "150") (name "unconnected-(J9-Pad7)") (class "Default")
      (node (ref "J9") (pin "7") (pinfunction "7_7") (pintype "passive+no_connect"))
    )
    (net (code "151") (name "unconnected-(J9-Pad12)") (class "Default")
      (node (ref "J9") (pin "12") (pinfunction "12_12") (pintype "passive+no_connect"))
    )
    (net (code "152") (name "unconnected-(J9-Pad14)") (class "Default")
      (node (ref "J9") (pin "14") (pinfunction "14_14") (pintype "passive+no_connect"))
    )
    (net (code "153") (name "unconnected-(J10-Pad4)") (class "Default")
      (node (ref "J10") (pin "4") (pinfunction "4_4") (pintype "passive+no_connect"))
    )
    (net (code "154") (name "unconnected-(J10-Pad6)") (class "Default")
      (node (ref "J10") (pin "6") (pinfunction "6_6") (pintype "passive+no_connect"))
    )
    (net (code "155") (name "unconnected-(J10-Pad7)") (class "Default")
      (node (ref "J10") (pin "7") (pinfunction "7_7") (pintype "passive+no_connect"))
    )
    (net (code "156") (name "unconnected-(J10-Pad12)") (class "Default")
      (node (ref "J10") (pin "12") (pinfunction "12_12") (pintype "passive+no_connect"))
    )
    (net (code "157") (name "unconnected-(J10-Pad14)") (class "Default")
      (node (ref "J10") (pin "14") (pinfunction "14_14") (pintype "passive+no_connect"))
    )
  )
)
